# Cineo-6-Channel_Buck_A1.net
KiCad netlist of a schematic drawn in EAGLE
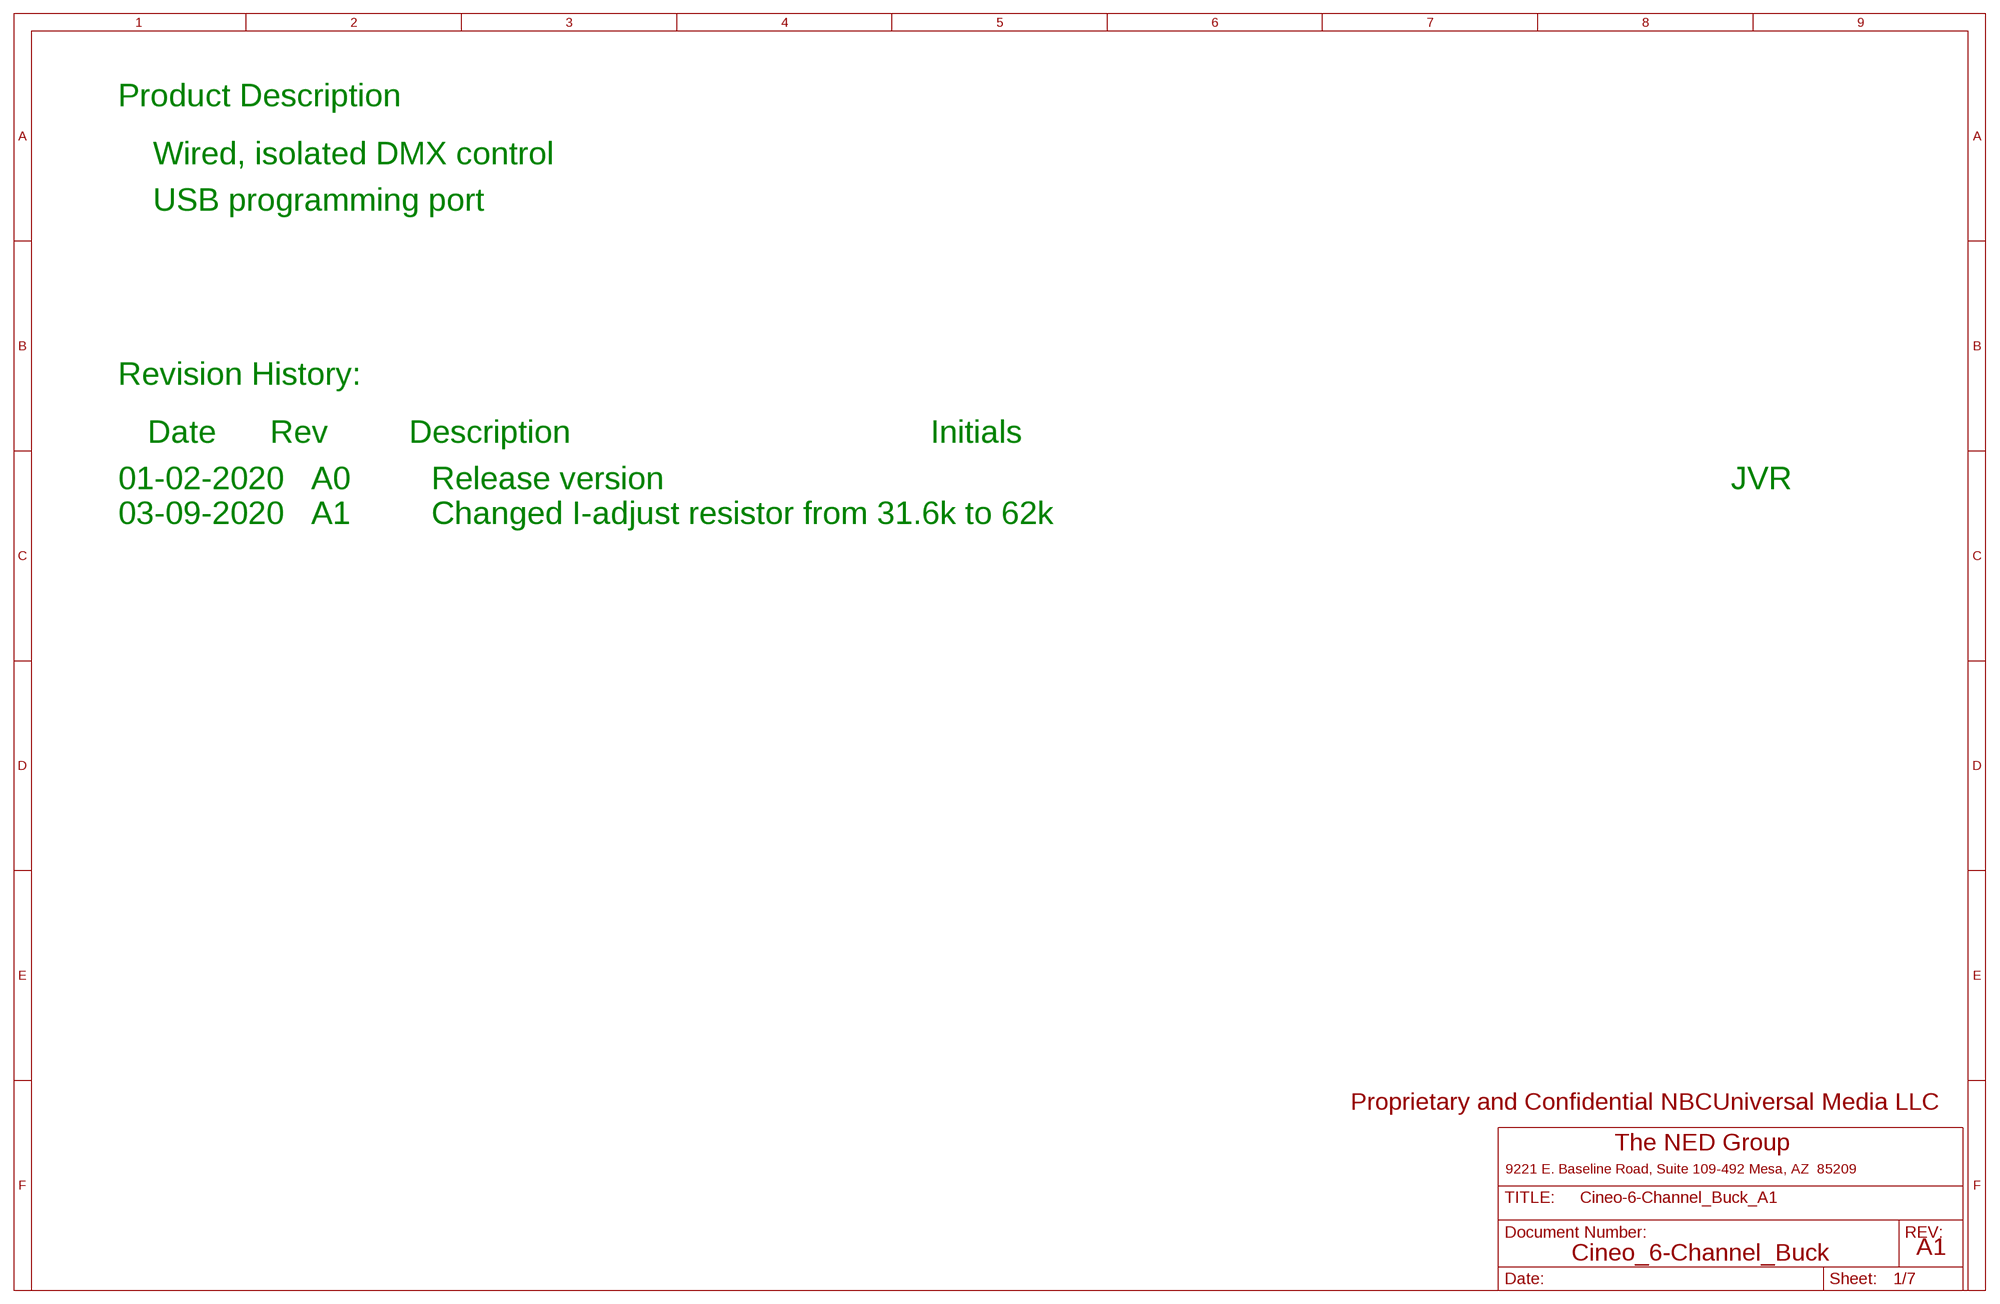
[diagram p0: schematic, sheet 1]
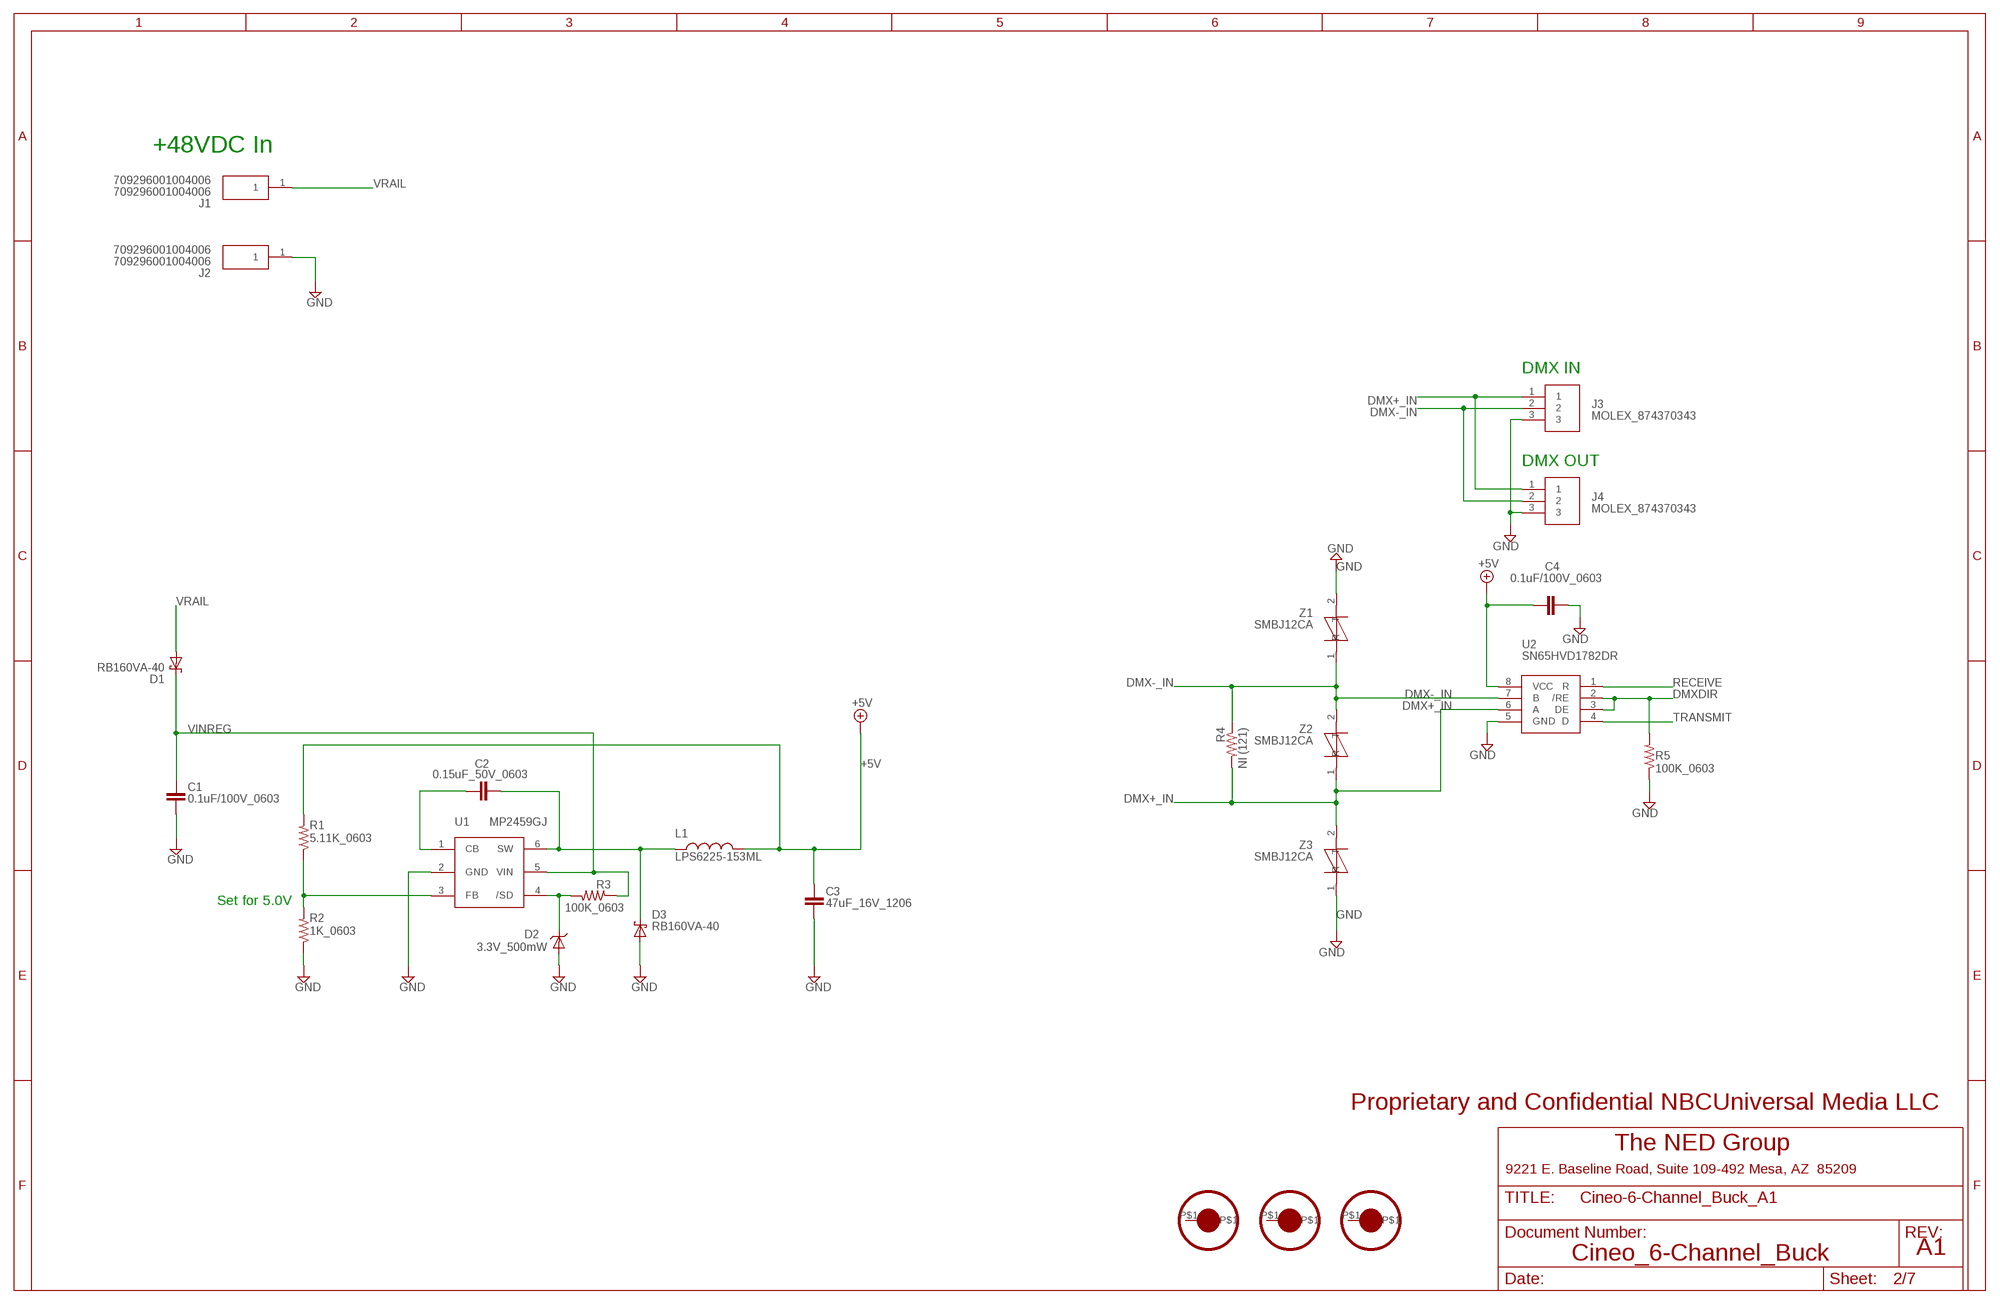
[diagram p1: schematic, sheet 2]
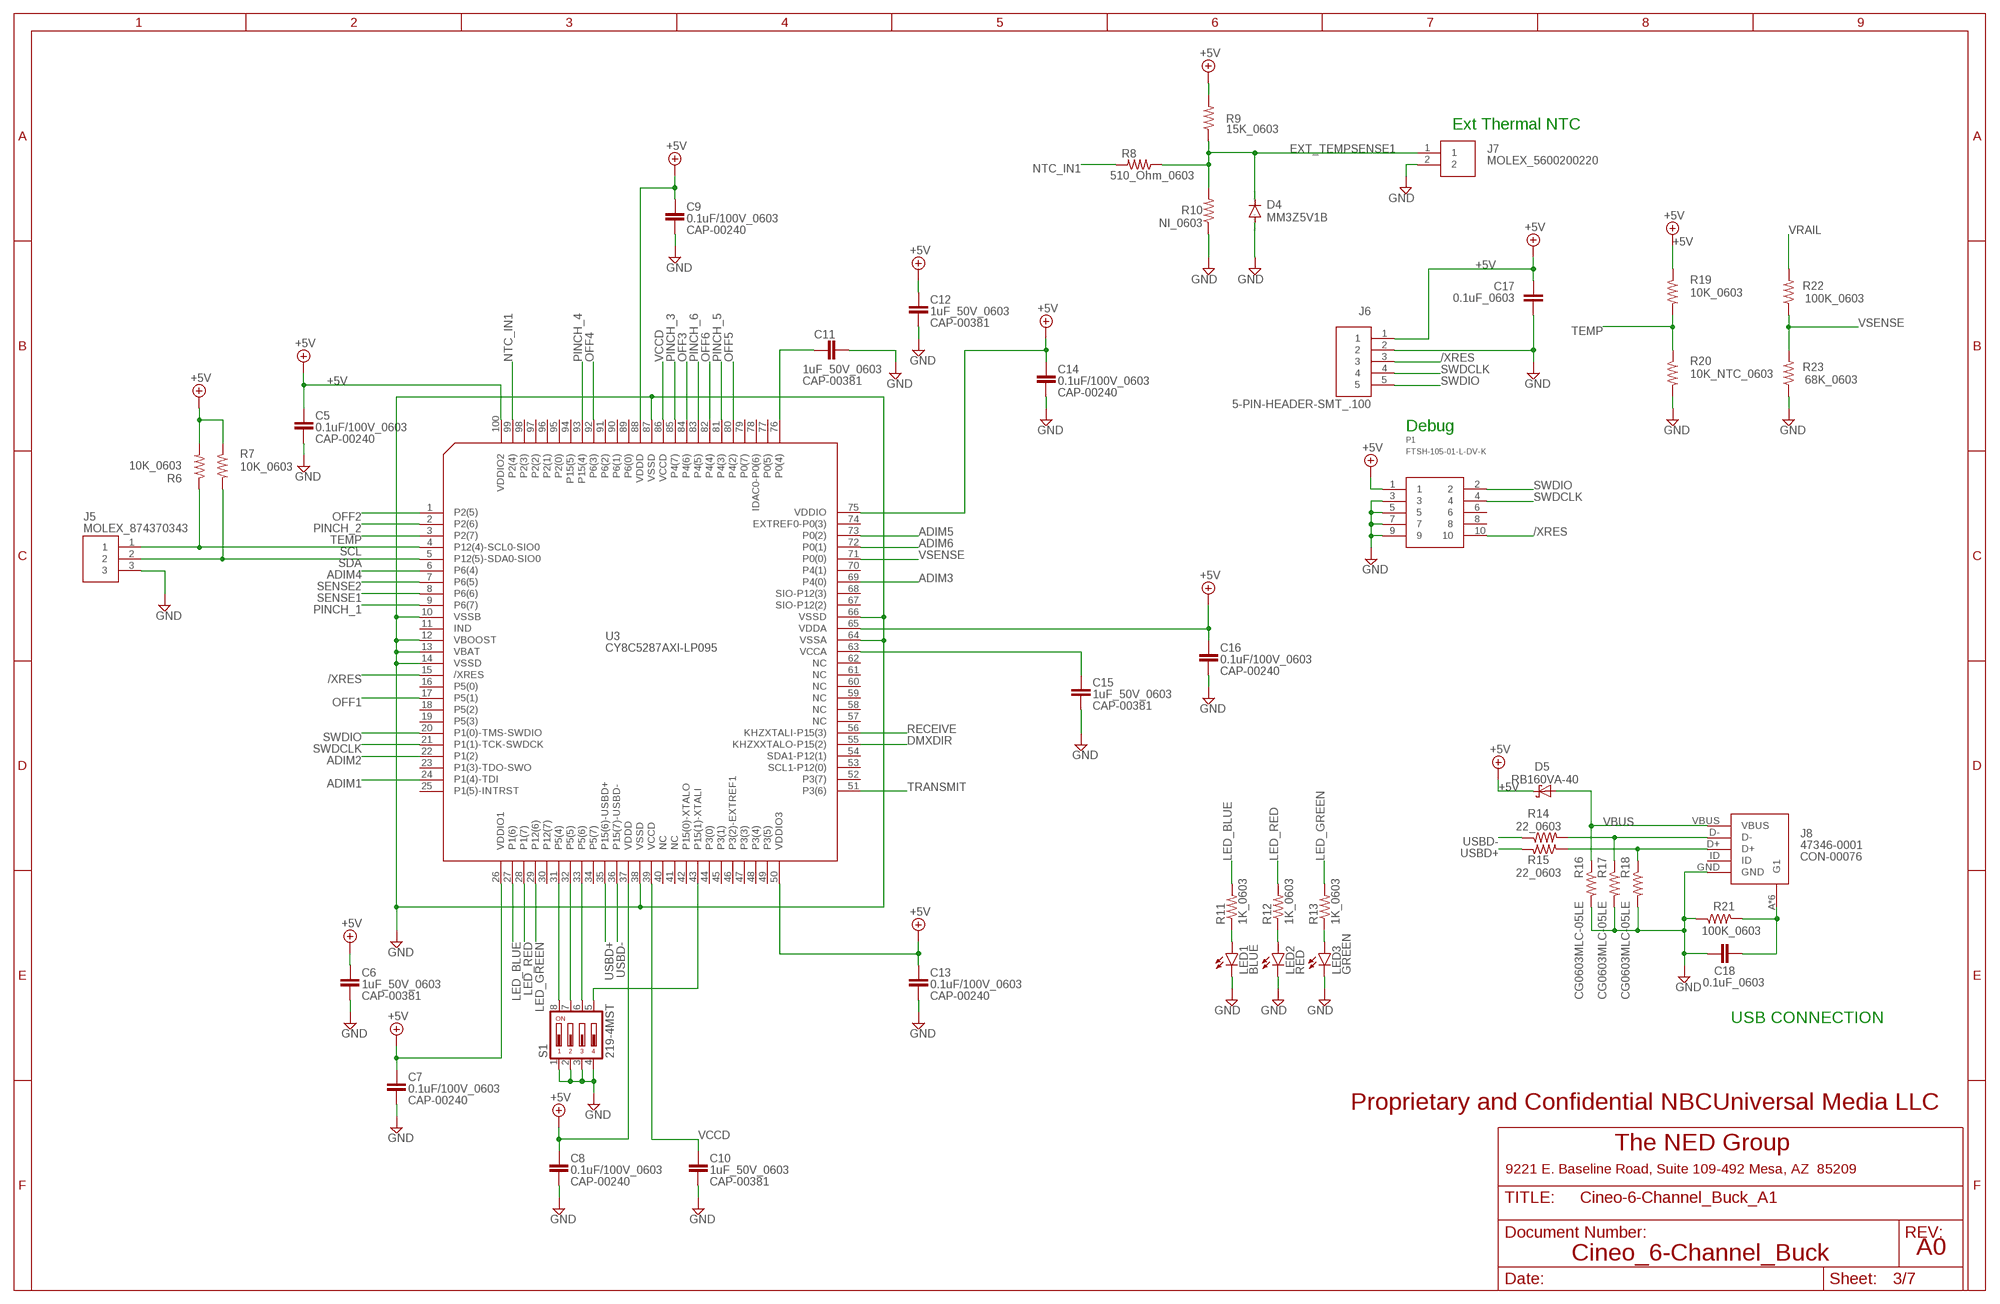
[diagram p2: schematic, sheet 3]
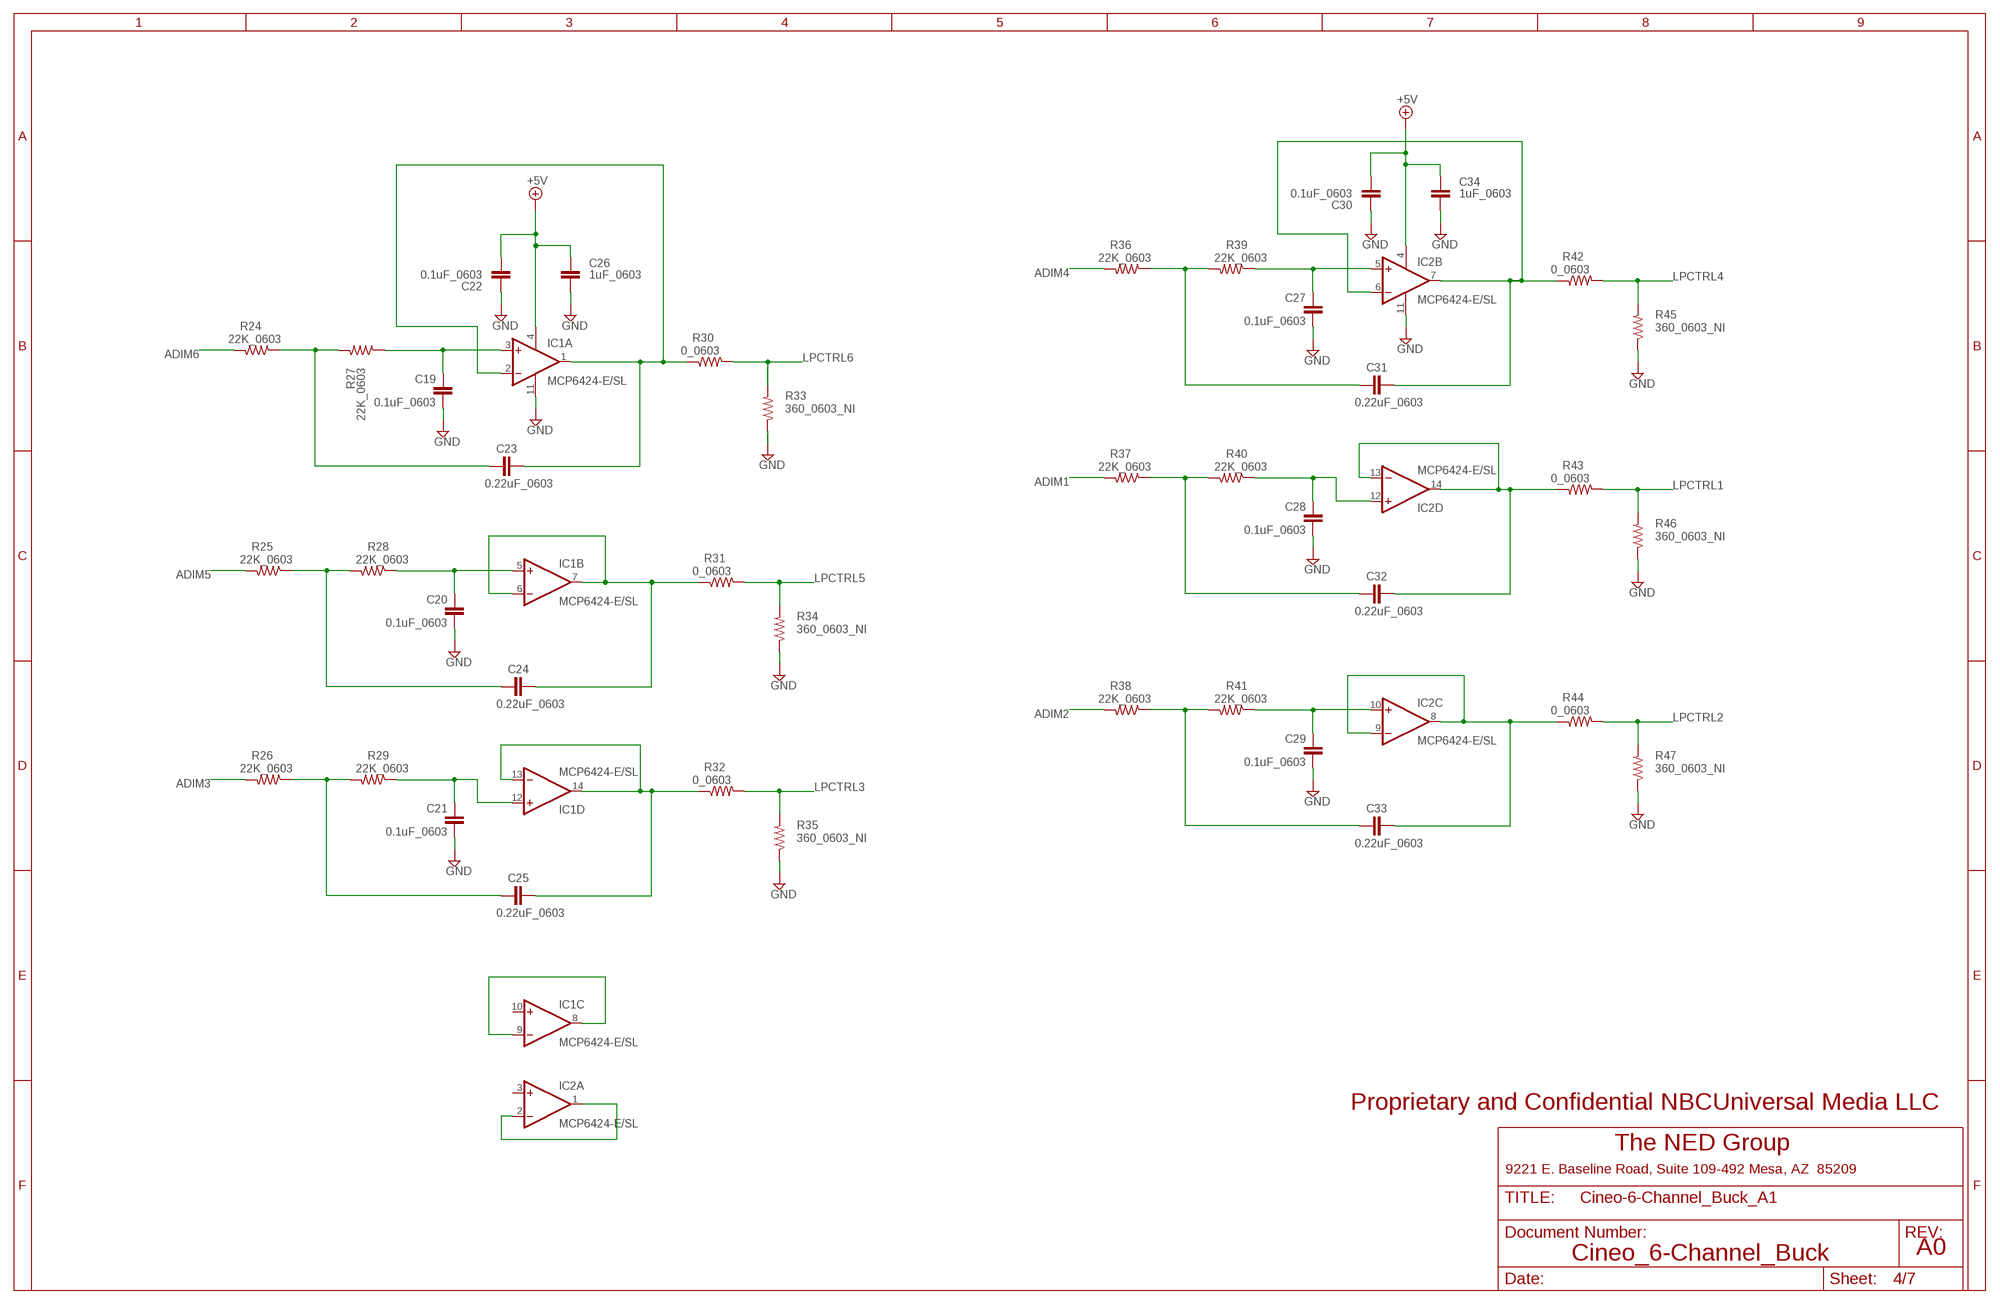
[diagram p3: schematic, sheet 4]
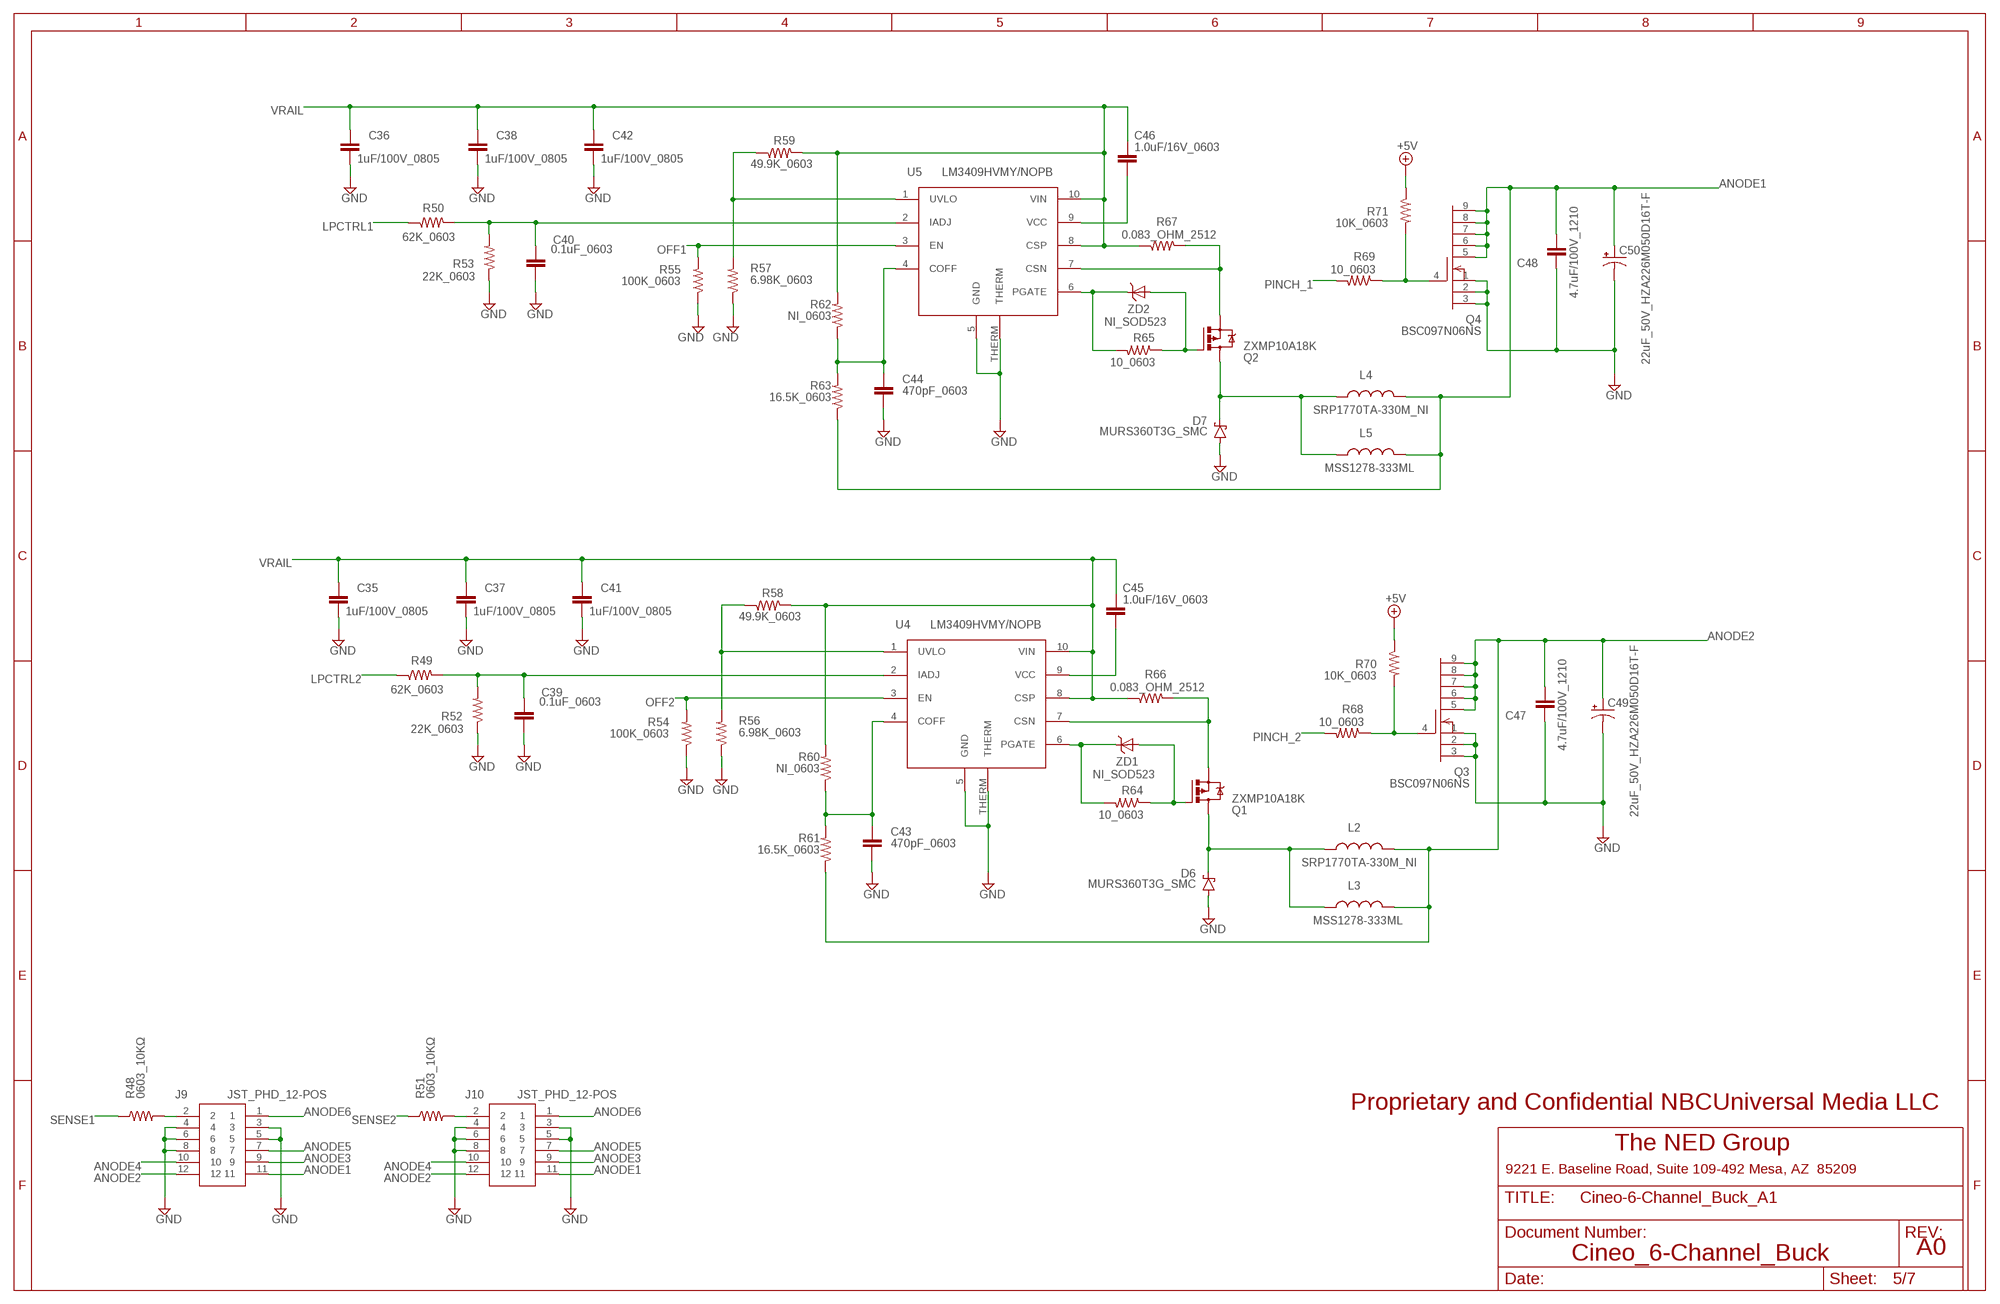
[diagram p4: schematic, sheet 5]
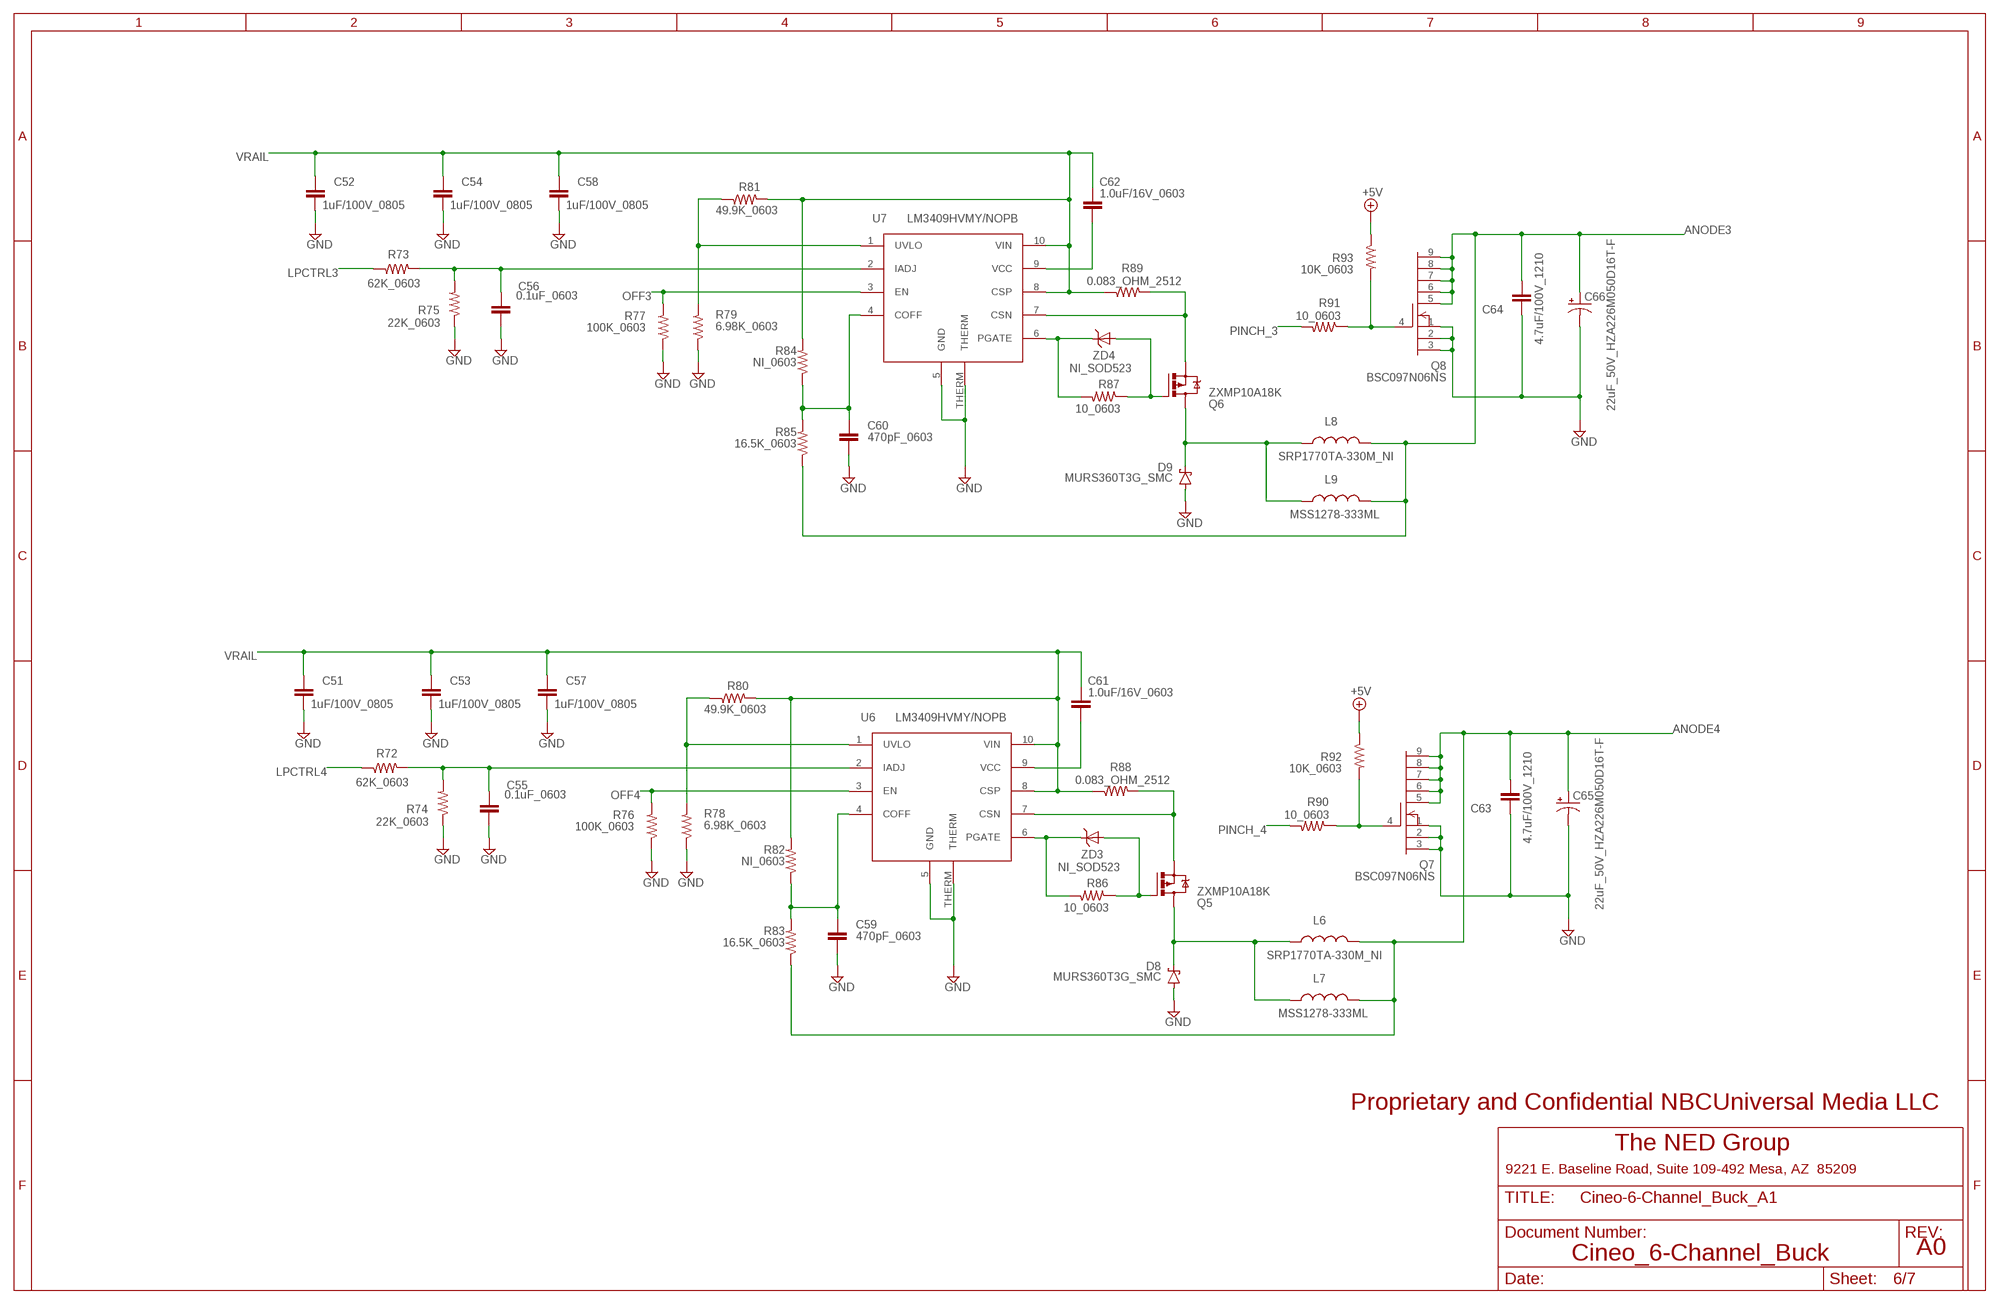
[diagram p5: schematic, sheet 6]
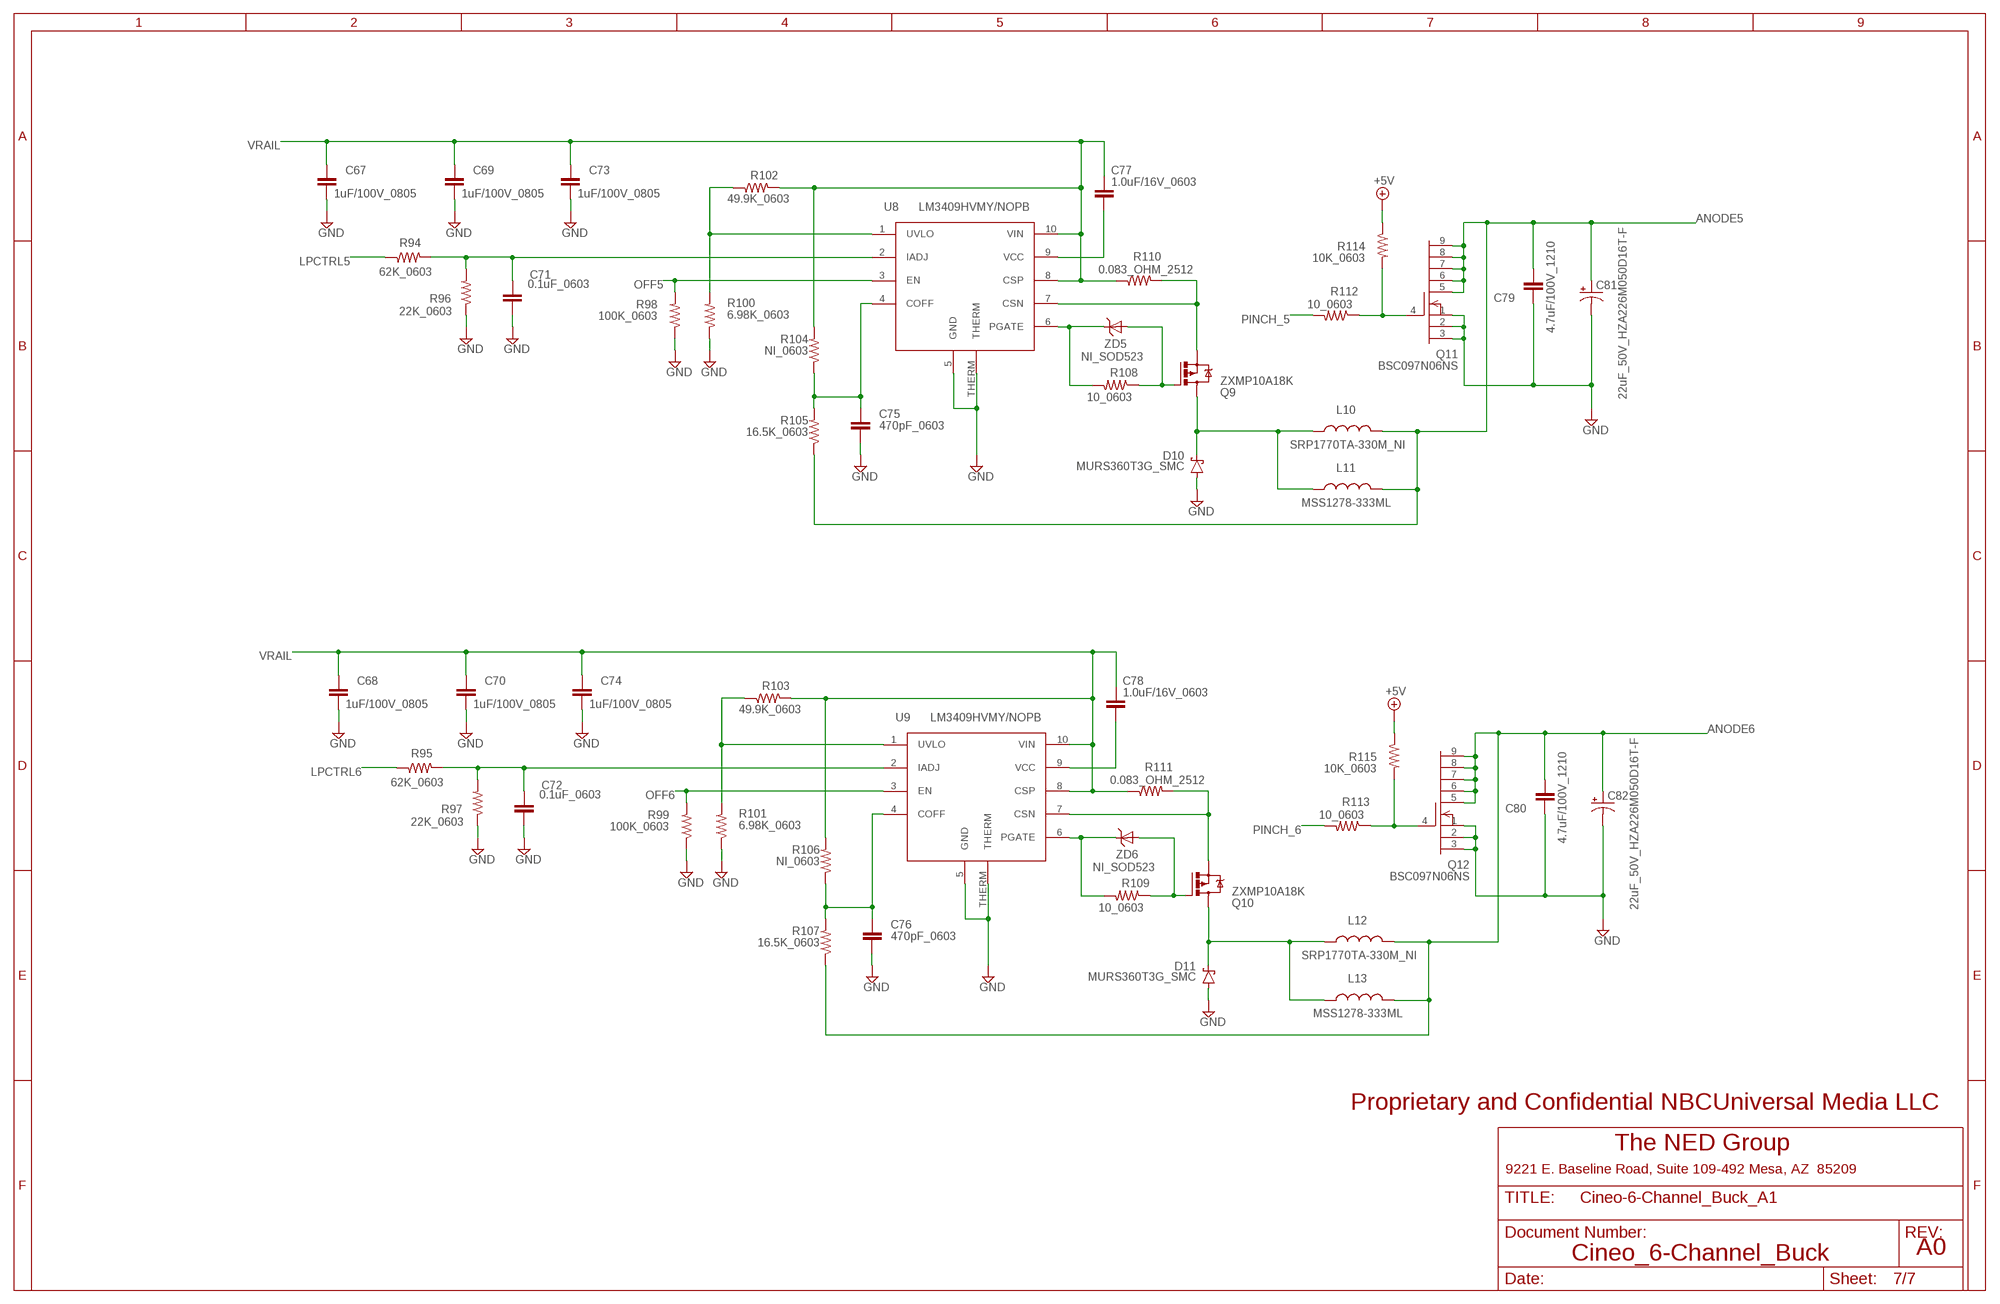
[diagram p6: schematic, sheet 7]

(export (version "E")
  (design (tool "Eeschema 10.0.6"))
  (components
    (comp (ref "C19")
      (value "0.1uF_0603")
      (footprint "eagle-import:C0603")
      (libsource (lib "eagle-import") (part "C-EUC0603"))
    )
    (comp (ref "C20")
      (value "0.1uF_0603")
      (footprint "eagle-import:C0603")
      (libsource (lib "eagle-import") (part "C-EUC0603"))
    )
    (comp (ref "C21")
      (value "0.1uF_0603")
      (footprint "eagle-import:C0603")
      (libsource (lib "eagle-import") (part "C-EUC0603"))
    )
    (comp (ref "C22")
      (value "0.1uF_0603")
      (footprint "eagle-import:C0603")
      (libsource (lib "eagle-import") (part "C-EUC0603"))
    )
    (comp (ref "C23")
      (value "0.22uF_0603")
      (footprint "eagle-import:C0603")
      (libsource (lib "eagle-import") (part "C-EUC0603"))
    )
    (comp (ref "C24")
      (value "0.22uF_0603")
      (footprint "eagle-import:C0603")
      (libsource (lib "eagle-import") (part "C-EUC0603"))
    )
    (comp (ref "C25")
      (value "0.22uF_0603")
      (footprint "eagle-import:C0603")
      (libsource (lib "eagle-import") (part "C-EUC0603"))
    )
    (comp (ref "C26")
      (value "1uF_0603")
      (footprint "eagle-import:C0603")
      (libsource (lib "eagle-import") (part "C-EUC0603"))
    )
    (comp (ref "C27")
      (value "0.1uF_0603")
      (footprint "eagle-import:C0603")
      (libsource (lib "eagle-import") (part "C-EUC0603"))
    )
    (comp (ref "C28")
      (value "0.1uF_0603")
      (footprint "eagle-import:C0603")
      (libsource (lib "eagle-import") (part "C-EUC0603"))
    )
    (comp (ref "C29")
      (value "0.1uF_0603")
      (footprint "eagle-import:C0603")
      (libsource (lib "eagle-import") (part "C-EUC0603"))
    )
    (comp (ref "C30")
      (value "0.1uF_0603")
      (footprint "eagle-import:C0603")
      (libsource (lib "eagle-import") (part "C-EUC0603"))
    )
    (comp (ref "C31")
      (value "0.22uF_0603")
      (footprint "eagle-import:C0603")
      (libsource (lib "eagle-import") (part "C-EUC0603"))
    )
    (comp (ref "C32")
      (value "0.22uF_0603")
      (footprint "eagle-import:C0603")
      (libsource (lib "eagle-import") (part "C-EUC0603"))
    )
    (comp (ref "C33")
      (value "0.22uF_0603")
      (footprint "eagle-import:C0603")
      (libsource (lib "eagle-import") (part "C-EUC0603"))
    )
    (comp (ref "C34")
      (value "1uF_0603")
      (footprint "eagle-import:C0603")
      (libsource (lib "eagle-import") (part "C-EUC0603"))
    )
    (comp (ref "IC1")
      (value "MCP6424-E/SL")
      (footprint "eagle-import:SO14")
      (libsource (lib "eagle-import") (part "TLC274D"))
    )
    (comp (ref "IC2")
      (value "MCP6424-E/SL")
      (footprint "eagle-import:SO14")
      (libsource (lib "eagle-import") (part "TLC274D"))
    )
    (comp (ref "R24")
      (value "22K_0603")
      (footprint "eagle-import:R0603")
      (libsource (lib "eagle-import") (part "R-US_R0603"))
    )
    (comp (ref "R25")
      (value "22K_0603")
      (footprint "eagle-import:R0603")
      (libsource (lib "eagle-import") (part "R-US_R0603"))
    )
    (comp (ref "R26")
      (value "22K_0603")
      (footprint "eagle-import:R0603")
      (libsource (lib "eagle-import") (part "R-US_R0603"))
    )
    (comp (ref "R27")
      (value "22K_0603")
      (footprint "eagle-import:R0603")
      (libsource (lib "eagle-import") (part "R-US_R0603"))
    )
    (comp (ref "R28")
      (value "22K_0603")
      (footprint "eagle-import:R0603")
      (libsource (lib "eagle-import") (part "R-US_R0603"))
    )
    (comp (ref "R29")
      (value "22K_0603")
      (footprint "eagle-import:R0603")
      (libsource (lib "eagle-import") (part "R-US_R0603"))
    )
    (comp (ref "R30")
      (value "0_0603")
      (footprint "eagle-import:R0603")
      (libsource (lib "eagle-import") (part "R-US_R0603"))
    )
    (comp (ref "R31")
      (value "0_0603")
      (footprint "eagle-import:R0603")
      (libsource (lib "eagle-import") (part "R-US_R0603"))
    )
    (comp (ref "R32")
      (value "0_0603")
      (footprint "eagle-import:R0603")
      (libsource (lib "eagle-import") (part "R-US_R0603"))
    )
    (comp (ref "R33")
      (value "360_0603_NI")
      (footprint "eagle-import:R0603")
      (libsource (lib "eagle-import") (part "R-US_R0603"))
    )
    (comp (ref "R34")
      (value "360_0603_NI")
      (footprint "eagle-import:R0603")
      (libsource (lib "eagle-import") (part "R-US_R0603"))
    )
    (comp (ref "R35")
      (value "360_0603_NI")
      (footprint "eagle-import:R0603")
      (libsource (lib "eagle-import") (part "R-US_R0603"))
    )
    (comp (ref "R36")
      (value "22K_0603")
      (footprint "eagle-import:R0603")
      (libsource (lib "eagle-import") (part "R-US_R0603"))
    )
    (comp (ref "R37")
      (value "22K_0603")
      (footprint "eagle-import:R0603")
      (libsource (lib "eagle-import") (part "R-US_R0603"))
    )
    (comp (ref "R38")
      (value "22K_0603")
      (footprint "eagle-import:R0603")
      (libsource (lib "eagle-import") (part "R-US_R0603"))
    )
    (comp (ref "R39")
      (value "22K_0603")
      (footprint "eagle-import:R0603")
      (libsource (lib "eagle-import") (part "R-US_R0603"))
    )
    (comp (ref "R40")
      (value "22K_0603")
      (footprint "eagle-import:R0603")
      (libsource (lib "eagle-import") (part "R-US_R0603"))
    )
    (comp (ref "R41")
      (value "22K_0603")
      (footprint "eagle-import:R0603")
      (libsource (lib "eagle-import") (part "R-US_R0603"))
    )
    (comp (ref "R42")
      (value "0_0603")
      (footprint "eagle-import:R0603")
      (libsource (lib "eagle-import") (part "R-US_R0603"))
    )
    (comp (ref "R43")
      (value "0_0603")
      (footprint "eagle-import:R0603")
      (libsource (lib "eagle-import") (part "R-US_R0603"))
    )
    (comp (ref "R44")
      (value "0_0603")
      (footprint "eagle-import:R0603")
      (libsource (lib "eagle-import") (part "R-US_R0603"))
    )
    (comp (ref "R45")
      (value "360_0603_NI")
      (footprint "eagle-import:R0603")
      (libsource (lib "eagle-import") (part "R-US_R0603"))
    )
    (comp (ref "R46")
      (value "360_0603_NI")
      (footprint "eagle-import:R0603")
      (libsource (lib "eagle-import") (part "R-US_R0603"))
    )
    (comp (ref "R47")
      (value "360_0603_NI")
      (footprint "eagle-import:R0603")
      (libsource (lib "eagle-import") (part "R-US_R0603"))
    )
    (comp (ref "C67")
      (value "1uF/100V_0805")
      (footprint "eagle-import:C0805")
      (libsource (lib "eagle-import") (part "C-EUC0805"))
    )
    (comp (ref "C68")
      (value "1uF/100V_0805")
      (footprint "eagle-import:C0805")
      (libsource (lib "eagle-import") (part "C-EUC0805"))
    )
    (comp (ref "C69")
      (value "1uF/100V_0805")
      (footprint "eagle-import:C0805")
      (libsource (lib "eagle-import") (part "C-EUC0805"))
    )
    (comp (ref "C70")
      (value "1uF/100V_0805")
      (footprint "eagle-import:C0805")
      (libsource (lib "eagle-import") (part "C-EUC0805"))
    )
    (comp (ref "C71")
      (value "0.1uF_0603")
      (footprint "eagle-import:C0603")
      (libsource (lib "eagle-import") (part "C-EUC0603"))
    )
    (comp (ref "C72")
      (value "0.1uF_0603")
      (footprint "eagle-import:C0603")
      (libsource (lib "eagle-import") (part "C-EUC0603"))
    )
    (comp (ref "C73")
      (value "1uF/100V_0805")
      (footprint "eagle-import:C0805")
      (libsource (lib "eagle-import") (part "C-EUC0805"))
    )
    (comp (ref "C74")
      (value "1uF/100V_0805")
      (footprint "eagle-import:C0805")
      (libsource (lib "eagle-import") (part "C-EUC0805"))
    )
    (comp (ref "C75")
      (value "470pF_0603")
      (footprint "eagle-import:C0603")
      (libsource (lib "eagle-import") (part "C-EUC0603"))
    )
    (comp (ref "C76")
      (value "470pF_0603")
      (footprint "eagle-import:C0603")
      (libsource (lib "eagle-import") (part "C-EUC0603"))
    )
    (comp (ref "C77")
      (value "1.0uF/16V_0603")
      (footprint "eagle-import:C0603")
      (libsource (lib "eagle-import") (part "C-EUC0603"))
    )
    (comp (ref "C78")
      (value "1.0uF/16V_0603")
      (footprint "eagle-import:C0603")
      (libsource (lib "eagle-import") (part "C-EUC0603"))
    )
    (comp (ref "C79")
      (value "4.7uF/100V_1210")
      (footprint "eagle-import:C1210")
      (libsource (lib "eagle-import") (part "C-EUC1210"))
    )
    (comp (ref "C80")
      (value "4.7uF/100V_1210")
      (footprint "eagle-import:C1210")
      (libsource (lib "eagle-import") (part "C-EUC1210"))
    )
    (comp (ref "C81")
      (value "22uF_50V_HZA226M050D16T-F")
      (footprint "eagle-import:PANASONIC_D")
      (libsource (lib "eagle-import") (part "CPOL-USD"))
    )
    (comp (ref "C82")
      (value "22uF_50V_HZA226M050D16T-F")
      (footprint "eagle-import:PANASONIC_D")
      (libsource (lib "eagle-import") (part "CPOL-USD"))
    )
    (comp (ref "D10")
      (value "MURS360T3G_SMC")
      (footprint "eagle-import:SMC")
      (libsource (lib "eagle-import") (part "SCHOTTKY-DIODESMC"))
    )
    (comp (ref "D11")
      (value "MURS360T3G_SMC")
      (footprint "eagle-import:SMC")
      (libsource (lib "eagle-import") (part "SCHOTTKY-DIODESMC"))
    )
    (comp (ref "L10")
      (value "SRP1770TA-330M_NI")
      (footprint "eagle-import:BOURNS_SRP1770TA")
      (libsource (lib "eagle-import") (part "BOURNS_SRP1770TA"))
    )
    (comp (ref "L11")
      (value "MSS1278-333ML")
      (footprint "eagle-import:MSS1260")
      (libsource (lib "eagle-import") (part "COILCRAFT_MSS1260"))
    )
    (comp (ref "L12")
      (value "SRP1770TA-330M_NI")
      (footprint "eagle-import:BOURNS_SRP1770TA")
      (libsource (lib "eagle-import") (part "BOURNS_SRP1770TA"))
    )
    (comp (ref "L13")
      (value "MSS1278-333ML")
      (footprint "eagle-import:MSS1260")
      (libsource (lib "eagle-import") (part "COILCRAFT_MSS1260"))
    )
    (comp (ref "Q9")
      (value "ZXMP10A18K")
      (footprint "eagle-import:DPAK")
      (libsource (lib "eagle-import") (part "MOSFET_P-CHANNEL_3LEADTAB_SOURCE"))
    )
    (comp (ref "Q10")
      (value "ZXMP10A18K")
      (footprint "eagle-import:DPAK")
      (libsource (lib "eagle-import") (part "MOSFET_P-CHANNEL_3LEADTAB_SOURCE"))
    )
    (comp (ref "Q11")
      (value "BSC097N06NS")
      (footprint "eagle-import:SO-8_POWERPAC")
      (libsource (lib "eagle-import") (part "SI7464DP_SO8_POWERPAC"))
    )
    (comp (ref "Q12")
      (value "BSC097N06NS")
      (footprint "eagle-import:SO-8_POWERPAC")
      (libsource (lib "eagle-import") (part "SI7464DP_SO8_POWERPAC"))
    )
    (comp (ref "R94")
      (value "62K_0603")
      (footprint "eagle-import:R0603")
      (libsource (lib "eagle-import") (part "R-US_R0603"))
    )
    (comp (ref "R95")
      (value "62K_0603")
      (footprint "eagle-import:R0603")
      (libsource (lib "eagle-import") (part "R-US_R0603"))
    )
    (comp (ref "R96")
      (value "22K_0603")
      (footprint "eagle-import:R0603")
      (libsource (lib "eagle-import") (part "R-US_R0603"))
    )
    (comp (ref "R97")
      (value "22K_0603")
      (footprint "eagle-import:R0603")
      (libsource (lib "eagle-import") (part "R-US_R0603"))
    )
    (comp (ref "R98")
      (value "100K_0603")
      (footprint "eagle-import:R0603")
      (libsource (lib "eagle-import") (part "R-US_R0603"))
    )
    (comp (ref "R99")
      (value "100K_0603")
      (footprint "eagle-import:R0603")
      (libsource (lib "eagle-import") (part "R-US_R0603"))
    )
    (comp (ref "R100")
      (value "6.98K_0603")
      (footprint "eagle-import:R0603")
      (libsource (lib "eagle-import") (part "R-US_R0603"))
    )
    (comp (ref "R101")
      (value "6.98K_0603")
      (footprint "eagle-import:R0603")
      (libsource (lib "eagle-import") (part "R-US_R0603"))
    )
    (comp (ref "R102")
      (value "49.9K_0603")
      (footprint "eagle-import:R0603")
      (libsource (lib "eagle-import") (part "R-US_R0603"))
    )
    (comp (ref "R103")
      (value "49.9K_0603")
      (footprint "eagle-import:R0603")
      (libsource (lib "eagle-import") (part "R-US_R0603"))
    )
    (comp (ref "R104")
      (value "NI_0603")
      (footprint "eagle-import:R0603")
      (libsource (lib "eagle-import") (part "R-US_R0603"))
    )
    (comp (ref "R105")
      (value "16.5K_0603")
      (footprint "eagle-import:R0603")
      (libsource (lib "eagle-import") (part "R-US_R0603"))
    )
    (comp (ref "R106")
      (value "NI_0603")
      (footprint "eagle-import:R0603")
      (libsource (lib "eagle-import") (part "R-US_R0603"))
    )
    (comp (ref "R107")
      (value "16.5K_0603")
      (footprint "eagle-import:R0603")
      (libsource (lib "eagle-import") (part "R-US_R0603"))
    )
    (comp (ref "R108")
      (value "10_0603")
      (footprint "eagle-import:R0603")
      (libsource (lib "eagle-import") (part "R-US_R0603"))
    )
    (comp (ref "R109")
      (value "10_0603")
      (footprint "eagle-import:R0603")
      (libsource (lib "eagle-import") (part "R-US_R0603"))
    )
    (comp (ref "R110")
      (value "0.083_OHM_2512")
      (footprint "eagle-import:R2512")
      (libsource (lib "eagle-import") (part "R-US_R2512"))
    )
    (comp (ref "R111")
      (value "0.083_OHM_2512")
      (footprint "eagle-import:R2512")
      (libsource (lib "eagle-import") (part "R-US_R2512"))
    )
    (comp (ref "R112")
      (value "10_0603")
      (footprint "eagle-import:R0603")
      (libsource (lib "eagle-import") (part "R-US_R0603"))
    )
    (comp (ref "R113")
      (value "10_0603")
      (footprint "eagle-import:R0603")
      (libsource (lib "eagle-import") (part "R-US_R0603"))
    )
    (comp (ref "R114")
      (value "10K_0603")
      (footprint "eagle-import:R0603")
      (libsource (lib "eagle-import") (part "R-US_R0603"))
    )
    (comp (ref "R115")
      (value "10K_0603")
      (footprint "eagle-import:R0603")
      (libsource (lib "eagle-import") (part "R-US_R0603"))
    )
    (comp (ref "U8")
      (value "LM3409HVMY/NOPB")
      (footprint "eagle-import:MSOP10-THERMALENHANCED")
      (libsource (lib "eagle-import") (part "LM3409HV"))
    )
    (comp (ref "U9")
      (value "LM3409HVMY/NOPB")
      (footprint "eagle-import:MSOP10-THERMALENHANCED")
      (libsource (lib "eagle-import") (part "LM3409HV"))
    )
    (comp (ref "ZD5")
      (value "NI_SOD523")
      (footprint "eagle-import:SOD-523")
      (libsource (lib "eagle-import") (part "ZENER_SOD-523"))
    )
    (comp (ref "ZD6")
      (value "NI_SOD523")
      (footprint "eagle-import:SOD-523")
      (libsource (lib "eagle-import") (part "ZENER_SOD-523"))
    )
    (comp (ref "C35")
      (value "1uF/100V_0805")
      (footprint "eagle-import:C0805")
      (libsource (lib "eagle-import") (part "C-EUC0805"))
    )
    (comp (ref "C36")
      (value "1uF/100V_0805")
      (footprint "eagle-import:C0805")
      (libsource (lib "eagle-import") (part "C-EUC0805"))
    )
    (comp (ref "C37")
      (value "1uF/100V_0805")
      (footprint "eagle-import:C0805")
      (libsource (lib "eagle-import") (part "C-EUC0805"))
    )
    (comp (ref "C38")
      (value "1uF/100V_0805")
      (footprint "eagle-import:C0805")
      (libsource (lib "eagle-import") (part "C-EUC0805"))
    )
    (comp (ref "C39")
      (value "0.1uF_0603")
      (footprint "eagle-import:C0603")
      (libsource (lib "eagle-import") (part "C-EUC0603"))
    )
    (comp (ref "C40")
      (value "0.1uF_0603")
      (footprint "eagle-import:C0603")
      (libsource (lib "eagle-import") (part "C-EUC0603"))
    )
    (comp (ref "C41")
      (value "1uF/100V_0805")
      (footprint "eagle-import:C0805")
      (libsource (lib "eagle-import") (part "C-EUC0805"))
    )
    (comp (ref "C42")
      (value "1uF/100V_0805")
      (footprint "eagle-import:C0805")
      (libsource (lib "eagle-import") (part "C-EUC0805"))
    )
    (comp (ref "C43")
      (value "470pF_0603")
      (footprint "eagle-import:C0603")
      (libsource (lib "eagle-import") (part "C-EUC0603"))
    )
    (comp (ref "C44")
      (value "470pF_0603")
      (footprint "eagle-import:C0603")
      (libsource (lib "eagle-import") (part "C-EUC0603"))
    )
    (comp (ref "C45")
      (value "1.0uF/16V_0603")
      (footprint "eagle-import:C0603")
      (libsource (lib "eagle-import") (part "C-EUC0603"))
    )
    (comp (ref "C46")
      (value "1.0uF/16V_0603")
      (footprint "eagle-import:C0603")
      (libsource (lib "eagle-import") (part "C-EUC0603"))
    )
    (comp (ref "C47")
      (value "4.7uF/100V_1210")
      (footprint "eagle-import:C1210")
      (libsource (lib "eagle-import") (part "C-EUC1210"))
    )
    (comp (ref "C48")
      (value "4.7uF/100V_1210")
      (footprint "eagle-import:C1210")
      (libsource (lib "eagle-import") (part "C-EUC1210"))
    )
    (comp (ref "C49")
      (value "22uF_50V_HZA226M050D16T-F")
      (footprint "eagle-import:PANASONIC_D")
      (libsource (lib "eagle-import") (part "CPOL-USD"))
    )
    (comp (ref "C50")
      (value "22uF_50V_HZA226M050D16T-F")
      (footprint "eagle-import:PANASONIC_D")
      (libsource (lib "eagle-import") (part "CPOL-USD"))
    )
    (comp (ref "D6")
      (value "MURS360T3G_SMC")
      (footprint "eagle-import:SMC")
      (libsource (lib "eagle-import") (part "SCHOTTKY-DIODESMC"))
    )
    (comp (ref "D7")
      (value "MURS360T3G_SMC")
      (footprint "eagle-import:SMC")
      (libsource (lib "eagle-import") (part "SCHOTTKY-DIODESMC"))
    )
    (comp (ref "J9")
      (value "JST_PHD_12-POS")
      (footprint "eagle-import:JST_PHD_12-POS")
      (libsource (lib "eagle-import") (part "JST_PHD_12-POS"))
    )
    (comp (ref "J10")
      (value "JST_PHD_12-POS")
      (footprint "eagle-import:JST_PHD_12-POS")
      (libsource (lib "eagle-import") (part "JST_PHD_12-POS"))
    )
    (comp (ref "L2")
      (value "SRP1770TA-330M_NI")
      (footprint "eagle-import:BOURNS_SRP1770TA")
      (libsource (lib "eagle-import") (part "BOURNS_SRP1770TA"))
    )
    (comp (ref "L3")
      (value "MSS1278-333ML")
      (footprint "eagle-import:MSS1260")
      (libsource (lib "eagle-import") (part "COILCRAFT_MSS1260"))
    )
    (comp (ref "L4")
      (value "SRP1770TA-330M_NI")
      (footprint "eagle-import:BOURNS_SRP1770TA")
      (libsource (lib "eagle-import") (part "BOURNS_SRP1770TA"))
    )
    (comp (ref "L5")
      (value "MSS1278-333ML")
      (footprint "eagle-import:MSS1260")
      (libsource (lib "eagle-import") (part "COILCRAFT_MSS1260"))
    )
    (comp (ref "Q1")
      (value "ZXMP10A18K")
      (footprint "eagle-import:DPAK")
      (libsource (lib "eagle-import") (part "MOSFET_P-CHANNEL_3LEADTAB_SOURCE"))
    )
    (comp (ref "Q2")
      (value "ZXMP10A18K")
      (footprint "eagle-import:DPAK")
      (libsource (lib "eagle-import") (part "MOSFET_P-CHANNEL_3LEADTAB_SOURCE"))
    )
    (comp (ref "Q3")
      (value "BSC097N06NS")
      (footprint "eagle-import:SO-8_POWERPAC")
      (libsource (lib "eagle-import") (part "SI7464DP_SO8_POWERPAC"))
    )
    (comp (ref "Q4")
      (value "BSC097N06NS")
      (footprint "eagle-import:SO-8_POWERPAC")
      (libsource (lib "eagle-import") (part "SI7464DP_SO8_POWERPAC"))
    )
    (comp (ref "R48")
      (value "0603_10KΩ")
      (footprint "eagle-import:R0603")
      (fields (field (name "PART_NUM") "RES-00001"))
      (libsource (lib "eagle-import") (part "0603_10KΩ"))
    )
    (comp (ref "R49")
      (value "62K_0603")
      (footprint "eagle-import:R0603")
      (libsource (lib "eagle-import") (part "R-US_R0603"))
    )
    (comp (ref "R50")
      (value "62K_0603")
      (footprint "eagle-import:R0603")
      (libsource (lib "eagle-import") (part "R-US_R0603"))
    )
    (comp (ref "R51")
      (value "0603_10KΩ")
      (footprint "eagle-import:R0603")
      (fields (field (name "PART_NUM") "RES-00001"))
      (libsource (lib "eagle-import") (part "0603_10KΩ"))
    )
    (comp (ref "R52")
      (value "22K_0603")
      (footprint "eagle-import:R0603")
      (libsource (lib "eagle-import") (part "R-US_R0603"))
    )
    (comp (ref "R53")
      (value "22K_0603")
      (footprint "eagle-import:R0603")
      (libsource (lib "eagle-import") (part "R-US_R0603"))
    )
    (comp (ref "R54")
      (value "100K_0603")
      (footprint "eagle-import:R0603")
      (libsource (lib "eagle-import") (part "R-US_R0603"))
    )
    (comp (ref "R55")
      (value "100K_0603")
      (footprint "eagle-import:R0603")
      (libsource (lib "eagle-import") (part "R-US_R0603"))
    )
    (comp (ref "R56")
      (value "6.98K_0603")
      (footprint "eagle-import:R0603")
      (libsource (lib "eagle-import") (part "R-US_R0603"))
    )
    (comp (ref "R57")
      (value "6.98K_0603")
      (footprint "eagle-import:R0603")
      (libsource (lib "eagle-import") (part "R-US_R0603"))
    )
    (comp (ref "R58")
      (value "49.9K_0603")
      (footprint "eagle-import:R0603")
      (libsource (lib "eagle-import") (part "R-US_R0603"))
    )
    (comp (ref "R59")
      (value "49.9K_0603")
      (footprint "eagle-import:R0603")
      (libsource (lib "eagle-import") (part "R-US_R0603"))
    )
    (comp (ref "R60")
      (value "NI_0603")
      (footprint "eagle-import:R0603")
      (libsource (lib "eagle-import") (part "R-US_R0603"))
    )
    (comp (ref "R61")
      (value "16.5K_0603")
      (footprint "eagle-import:R0603")
      (libsource (lib "eagle-import") (part "R-US_R0603"))
    )
    (comp (ref "R62")
      (value "NI_0603")
      (footprint "eagle-import:R0603")
      (libsource (lib "eagle-import") (part "R-US_R0603"))
    )
    (comp (ref "R63")
      (value "16.5K_0603")
      (footprint "eagle-import:R0603")
      (libsource (lib "eagle-import") (part "R-US_R0603"))
    )
    (comp (ref "R64")
      (value "10_0603")
      (footprint "eagle-import:R0603")
      (libsource (lib "eagle-import") (part "R-US_R0603"))
    )
    (comp (ref "R65")
      (value "10_0603")
      (footprint "eagle-import:R0603")
      (libsource (lib "eagle-import") (part "R-US_R0603"))
    )
    (comp (ref "R66")
      (value "0.083_OHM_2512")
      (footprint "eagle-import:R2512")
      (libsource (lib "eagle-import") (part "R-US_R2512"))
    )
    (comp (ref "R67")
      (value "0.083_OHM_2512")
      (footprint "eagle-import:R2512")
      (libsource (lib "eagle-import") (part "R-US_R2512"))
    )
    (comp (ref "R68")
      (value "10_0603")
      (footprint "eagle-import:R0603")
      (libsource (lib "eagle-import") (part "R-US_R0603"))
    )
    (comp (ref "R69")
      (value "10_0603")
      (footprint "eagle-import:R0603")
      (libsource (lib "eagle-import") (part "R-US_R0603"))
    )
    (comp (ref "R70")
      (value "10K_0603")
      (footprint "eagle-import:R0603")
      (libsource (lib "eagle-import") (part "R-US_R0603"))
    )
    (comp (ref "R71")
      (value "10K_0603")
      (footprint "eagle-import:R0603")
      (libsource (lib "eagle-import") (part "R-US_R0603"))
    )
    (comp (ref "U4")
      (value "LM3409HVMY/NOPB")
      (footprint "eagle-import:MSOP10-THERMALENHANCED")
      (libsource (lib "eagle-import") (part "LM3409HV"))
    )
    (comp (ref "U5")
      (value "LM3409HVMY/NOPB")
      (footprint "eagle-import:MSOP10-THERMALENHANCED")
      (libsource (lib "eagle-import") (part "LM3409HV"))
    )
    (comp (ref "ZD1")
      (value "NI_SOD523")
      (footprint "eagle-import:SOD-523")
      (libsource (lib "eagle-import") (part "ZENER_SOD-523"))
    )
    (comp (ref "ZD2")
      (value "NI_SOD523")
      (footprint "eagle-import:SOD-523")
      (libsource (lib "eagle-import") (part "ZENER_SOD-523"))
    )
    (comp (ref "C5")
      (value "0.1uF/100V_0603")
      (footprint "eagle-import:C0603")
      (fields (field (name "PART_NUM") "CAP-00240"))
      (libsource (lib "eagle-import") (part "0603_0.1UF_100V"))
    )
    (comp (ref "C6")
      (value "1uF_50V_0603")
      (footprint "eagle-import:C0603")
      (fields (field (name "PART_NUM") "CAP-00381"))
      (libsource (lib "eagle-import") (part "0603_1UF_50V"))
    )
    (comp (ref "C7")
      (value "0.1uF/100V_0603")
      (footprint "eagle-import:C0603")
      (fields (field (name "PART_NUM") "CAP-00240"))
      (libsource (lib "eagle-import") (part "0603_0.1UF_100V"))
    )
    (comp (ref "C8")
      (value "0.1uF/100V_0603")
      (footprint "eagle-import:C0603")
      (fields (field (name "PART_NUM") "CAP-00240"))
      (libsource (lib "eagle-import") (part "0603_0.1UF_100V"))
    )
    (comp (ref "C9")
      (value "0.1uF/100V_0603")
      (footprint "eagle-import:C0603")
      (fields (field (name "PART_NUM") "CAP-00240"))
      (libsource (lib "eagle-import") (part "0603_0.1UF_100V"))
    )
    (comp (ref "C10")
      (value "1uF_50V_0603")
      (footprint "eagle-import:C0603")
      (fields (field (name "PART_NUM") "CAP-00381"))
      (libsource (lib "eagle-import") (part "0603_1UF_50V"))
    )
    (comp (ref "C11")
      (value "1uF_50V_0603")
      (footprint "eagle-import:C0603")
      (fields (field (name "PART_NUM") "CAP-00381"))
      (libsource (lib "eagle-import") (part "0603_1UF_50V"))
    )
    (comp (ref "C12")
      (value "1uF_50V_0603")
      (footprint "eagle-import:C0603")
      (fields (field (name "PART_NUM") "CAP-00381"))
      (libsource (lib "eagle-import") (part "0603_1UF_50V"))
    )
    (comp (ref "C13")
      (value "0.1uF/100V_0603")
      (footprint "eagle-import:C0603")
      (fields (field (name "PART_NUM") "CAP-00240"))
      (libsource (lib "eagle-import") (part "0603_0.1UF_100V"))
    )
    (comp (ref "C14")
      (value "0.1uF/100V_0603")
      (footprint "eagle-import:C0603")
      (fields (field (name "PART_NUM") "CAP-00240"))
      (libsource (lib "eagle-import") (part "0603_0.1UF_100V"))
    )
    (comp (ref "C15")
      (value "1uF_50V_0603")
      (footprint "eagle-import:C0603")
      (fields (field (name "PART_NUM") "CAP-00381"))
      (libsource (lib "eagle-import") (part "0603_1UF_50V"))
    )
    (comp (ref "C16")
      (value "0.1uF/100V_0603")
      (footprint "eagle-import:C0603")
      (fields (field (name "PART_NUM") "CAP-00240"))
      (libsource (lib "eagle-import") (part "0603_0.1UF_100V"))
    )
    (comp (ref "C17")
      (value "0.1uF_0603")
      (footprint "eagle-import:C0603")
      (libsource (lib "eagle-import") (part "C-EUC0603"))
    )
    (comp (ref "C18")
      (value "0.1uF_0603")
      (footprint "eagle-import:C0603")
      (libsource (lib "eagle-import") (part "C-EUC0603"))
    )
    (comp (ref "D4")
      (value "MM3Z5V1B")
      (footprint "eagle-import:SOD323-R")
      (libsource (lib "eagle-import") (part "DIODE-SOD323-R"))
    )
    (comp (ref "D5")
      (value "RB160VA-40")
      (footprint "eagle-import:TUMD2")
      (libsource (lib "eagle-import") (part "RSX051VA-30"))
    )
    (comp (ref "J5")
      (value "MOLEX_874370343")
      (footprint "eagle-import:MOLEX_874370343")
      (libsource (lib "eagle-import") (part "MOLEX_874370343"))
    )
    (comp (ref "J6")
      (value "5-PIN-HEADER-SMT_.100")
      (footprint "eagle-import:5-PIN_SMT_.100")
      (fields (field (name "PART_NUM") "NOT INSTALLED"))
      (libsource (lib "eagle-import") (part "5-PIN-HEADER-SMT_.100"))
    )
    (comp (ref "J7")
      (value "MOLEX_5600200220")
      (footprint "eagle-import:MOLEX_5600200220")
      (libsource (lib "eagle-import") (part "MOLEX_5600200220"))
    )
    (comp (ref "J8")
      (value "47346-0001")
      (footprint "eagle-import:MOLEX_47346")
      (fields (field (name "PART_NUM") "CON-00076"))
      (libsource (lib "eagle-import") (part "MOLEX_47346"))
    )
    (comp (ref "LED1")
      (value "BLUE")
      (footprint "eagle-import:CHIPLED_0805")
      (libsource (lib "eagle-import") (part "LEDCHIPLED_0805"))
    )
    (comp (ref "LED2")
      (value "RED")
      (footprint "eagle-import:CHIPLED_0805")
      (libsource (lib "eagle-import") (part "LEDCHIPLED_0805"))
    )
    (comp (ref "LED3")
      (value "GREEN")
      (footprint "eagle-import:CHIPLED_0805")
      (libsource (lib "eagle-import") (part "LEDCHIPLED_0805"))
    )
    (comp (ref "P1")
      (value "FTSH-105-01-L-DV-K")
      (footprint "eagle-import:SAMTEC_FTSH-105-01-L-DV-K")
      (fields (field (name "PART_NUM") "CON-00037"))
      (libsource (lib "eagle-import") (part "FTSH-105-01-L-DV-K"))
    )
    (comp (ref "R6")
      (value "10K_0603")
      (footprint "eagle-import:R0603")
      (libsource (lib "eagle-import") (part "R-US_R0603"))
    )
    (comp (ref "R7")
      (value "10K_0603")
      (footprint "eagle-import:R0603")
      (libsource (lib "eagle-import") (part "R-US_R0603"))
    )
    (comp (ref "R8")
      (value "510_Ohm_0603")
      (footprint "eagle-import:R0603")
      (libsource (lib "eagle-import") (part "R-US_R0603"))
    )
    (comp (ref "R9")
      (value "15K_0603")
      (footprint "eagle-import:R0603")
      (libsource (lib "eagle-import") (part "R-US_R0603"))
    )
    (comp (ref "R10")
      (value "NI_0603")
      (footprint "eagle-import:R0603")
      (libsource (lib "eagle-import") (part "R-US_R0603"))
    )
    (comp (ref "R11")
      (value "1K_0603")
      (footprint "eagle-import:R0603")
      (libsource (lib "eagle-import") (part "R-US_R0603"))
    )
    (comp (ref "R12")
      (value "1K_0603")
      (footprint "eagle-import:R0603")
      (libsource (lib "eagle-import") (part "R-US_R0603"))
    )
    (comp (ref "R13")
      (value "1K_0603")
      (footprint "eagle-import:R0603")
      (libsource (lib "eagle-import") (part "R-US_R0603"))
    )
    (comp (ref "R14")
      (value "22_0603")
      (footprint "eagle-import:R0603")
      (libsource (lib "eagle-import") (part "R-US_R0603"))
    )
    (comp (ref "R15")
      (value "22_0603")
      (footprint "eagle-import:R0603")
      (libsource (lib "eagle-import") (part "R-US_R0603"))
    )
    (comp (ref "R16")
      (value "CG0603MLC-05LE")
      (footprint "eagle-import:R0603")
      (libsource (lib "eagle-import") (part "R-US_R0603"))
    )
    (comp (ref "R17")
      (value "CG0603MLC-05LE")
      (footprint "eagle-import:R0603")
      (libsource (lib "eagle-import") (part "R-US_R0603"))
    )
    (comp (ref "R18")
      (value "CG0603MLC-05LE")
      (footprint "eagle-import:R0603")
      (libsource (lib "eagle-import") (part "R-US_R0603"))
    )
    (comp (ref "R19")
      (value "10K_0603")
      (footprint "eagle-import:R0603")
      (libsource (lib "eagle-import") (part "R-US_R0603"))
    )
    (comp (ref "R20")
      (value "10K_NTC_0603")
      (footprint "eagle-import:R0603")
      (libsource (lib "eagle-import") (part "R-US_R0603"))
    )
    (comp (ref "R21")
      (value "100K_0603")
      (footprint "eagle-import:R0603")
      (libsource (lib "eagle-import") (part "R-US_R0603"))
    )
    (comp (ref "R22")
      (value "100K_0603")
      (footprint "eagle-import:R0603")
      (libsource (lib "eagle-import") (part "R-US_R0603"))
    )
    (comp (ref "R23")
      (value "68K_0603")
      (footprint "eagle-import:R0603")
      (libsource (lib "eagle-import") (part "R-US_R0603"))
    )
    (comp (ref "S1")
      (value "219-4MST")
      (footprint "eagle-import:CTS-219-04")
      (libsource (lib "eagle-import") (part "219-04"))
    )
    (comp (ref "U3")
      (value "CY8C5287AXI-LP095")
      (footprint "eagle-import:TQFP100")
      (fields (field (name "PART_NUM") "ICC-00167"))
      (libsource (lib "eagle-import") (part "CYPRESS_CY8C52XX_100PIN5287"))
    )
    (comp (ref "C1")
      (value "0.1uF/100V_0603")
      (footprint "eagle-import:C0603")
      (fields (field (name "PART_NUM") "CAP-00240"))
      (libsource (lib "eagle-import") (part "0603_0.1UF_100V"))
    )
    (comp (ref "C2")
      (value "0.15uF_50V_0603")
      (footprint "eagle-import:C0603")
      (fields (field (name "PART_NUM") "CAP-00302"))
      (libsource (lib "eagle-import") (part "0603_0.15_50V"))
    )
    (comp (ref "C3")
      (value "47uF_16V_1206")
      (footprint "eagle-import:C1206")
      (fields (field (name "PART_NUM") "CAP-00301"))
      (libsource (lib "eagle-import") (part "1206_47UF_16V"))
    )
    (comp (ref "C4")
      (value "0.1uF/100V_0603")
      (footprint "eagle-import:C0603")
      (fields (field (name "PART_NUM") "CAP-00240"))
      (libsource (lib "eagle-import") (part "0603_0.1UF_100V"))
    )
    (comp (ref "D1")
      (value "RB160VA-40")
      (footprint "eagle-import:TUMD2")
      (fields (field (name "PART_NUM") "DIO-00001"))
      (libsource (lib "eagle-import") (part "ROHM_RB160VA-40"))
    )
    (comp (ref "D2")
      (value "3.3V_500mW")
      (footprint "eagle-import:SOD-123")
      (libsource (lib "eagle-import") (part "ZENERSOD-123"))
    )
    (comp (ref "D3")
      (value "RB160VA-40")
      (footprint "eagle-import:TUMD2")
      (fields (field (name "PART_NUM") "DIO-00001"))
      (libsource (lib "eagle-import") (part "ROHM_RB160VA-40"))
    )
    (comp (ref "FID1")
      (value "FIDUCIALSSMALLER")
      (footprint "eagle-import:FIDUCIAL_1MMX3MM")
      (fields (field (name "PART_NUM") "DNI-00000"))
      (libsource (lib "eagle-import") (part "FIDUCIALSSMALLER"))
    )
    (comp (ref "FID2")
      (value "FIDUCIALSSMALLER")
      (footprint "eagle-import:FIDUCIAL_1MMX3MM")
      (fields (field (name "PART_NUM") "DNI-00000"))
      (libsource (lib "eagle-import") (part "FIDUCIALSSMALLER"))
    )
    (comp (ref "FID3")
      (value "FIDUCIALSSMALLER")
      (footprint "eagle-import:FIDUCIAL_1MMX3MM")
      (fields (field (name "PART_NUM") "DNI-00000"))
      (libsource (lib "eagle-import") (part "FIDUCIALSSMALLER"))
    )
    (comp (ref "J1")
      (value "709296001004006")
      (footprint "eagle-import:AVX_709296001004006")
      (fields (field (name "PART_NUM") "CON-00273"))
      (libsource (lib "eagle-import") (part "AVX_709296001004006"))
    )
    (comp (ref "J2")
      (value "709296001004006")
      (footprint "eagle-import:AVX_709296001004006")
      (fields (field (name "PART_NUM") "CON-00273"))
      (libsource (lib "eagle-import") (part "AVX_709296001004006"))
    )
    (comp (ref "J3")
      (value "MOLEX_874370343")
      (footprint "eagle-import:MOLEX_874370343")
      (libsource (lib "eagle-import") (part "MOLEX_874370343"))
    )
    (comp (ref "J4")
      (value "MOLEX_874370343")
      (footprint "eagle-import:MOLEX_874370343")
      (libsource (lib "eagle-import") (part "MOLEX_874370343"))
    )
    (comp (ref "L1")
      (value "LPS6225-153ML")
      (footprint "eagle-import:COILCRAFT_LPS6235")
      (fields (field (name "PART_NUM") "IND-00128"))
      (libsource (lib "eagle-import") (part "COILCRAFT_LPS6225-153"))
    )
    (comp (ref "R1")
      (value "5.11K_0603")
      (footprint "eagle-import:R0603")
      (fields (field (name "PART_NUM") "RES-00263"))
      (libsource (lib "eagle-import") (part "Illum_RES_8639966_0603_5.11KΩ"))
    )
    (comp (ref "R2")
      (value "1K_0603")
      (footprint "eagle-import:R0603")
      (fields (field (name "PART_NUM") "RES-00002"))
      (libsource (lib "eagle-import") (part "Illum_RES_8639966_0603_1KΩ"))
    )
    (comp (ref "R3")
      (value "100K_0603")
      (footprint "eagle-import:R0603")
      (fields (field (name "PART_NUM") "RES-00015"))
      (libsource (lib "eagle-import") (part "Illum_RES_8639966_0603_100KΩ"))
    )
    (comp (ref "R4")
      (value "NI (121)")
      (footprint "eagle-import:R0603")
      (libsource (lib "eagle-import") (part "R-US_R0603"))
    )
    (comp (ref "R5")
      (value "100K_0603")
      (footprint "eagle-import:R0603")
      (libsource (lib "eagle-import") (part "R-US_R0603"))
    )
    (comp (ref "U1")
      (value "MP2459GJ")
      (footprint "eagle-import:TSOT_23-6")
      (fields (field (name "PART_NUM") "ICC-00074"))
      (libsource (lib "eagle-import") (part "MPS_MP2459GJ"))
    )
    (comp (ref "U2")
      (value "SN65HVD1782DR")
      (footprint "eagle-import:SO-8")
      (fields (field (name "PART_NUM") "ICC-00036"))
      (libsource (lib "eagle-import") (part "TI_SN65HVD1782DR"))
    )
    (comp (ref "Z1")
      (value "SMBJ12CA")
      (footprint "eagle-import:SMBJ")
      (libsource (lib "eagle-import") (part "TISP4360H3BJ"))
    )
    (comp (ref "Z2")
      (value "SMBJ12CA")
      (footprint "eagle-import:SMBJ")
      (libsource (lib "eagle-import") (part "TISP4360H3BJ"))
    )
    (comp (ref "Z3")
      (value "SMBJ12CA")
      (footprint "eagle-import:SMBJ")
      (libsource (lib "eagle-import") (part "TISP4360H3BJ"))
    )
    (comp (ref "C51")
      (value "1uF/100V_0805")
      (footprint "eagle-import:C0805")
      (libsource (lib "eagle-import") (part "C-EUC0805"))
    )
    (comp (ref "C52")
      (value "1uF/100V_0805")
      (footprint "eagle-import:C0805")
      (libsource (lib "eagle-import") (part "C-EUC0805"))
    )
    (comp (ref "C53")
      (value "1uF/100V_0805")
      (footprint "eagle-import:C0805")
      (libsource (lib "eagle-import") (part "C-EUC0805"))
    )
    (comp (ref "C54")
      (value "1uF/100V_0805")
      (footprint "eagle-import:C0805")
      (libsource (lib "eagle-import") (part "C-EUC0805"))
    )
    (comp (ref "C55")
      (value "0.1uF_0603")
      (footprint "eagle-import:C0603")
      (libsource (lib "eagle-import") (part "C-EUC0603"))
    )
    (comp (ref "C56")
      (value "0.1uF_0603")
      (footprint "eagle-import:C0603")
      (libsource (lib "eagle-import") (part "C-EUC0603"))
    )
    (comp (ref "C57")
      (value "1uF/100V_0805")
      (footprint "eagle-import:C0805")
      (libsource (lib "eagle-import") (part "C-EUC0805"))
    )
    (comp (ref "C58")
      (value "1uF/100V_0805")
      (footprint "eagle-import:C0805")
      (libsource (lib "eagle-import") (part "C-EUC0805"))
    )
    (comp (ref "C59")
      (value "470pF_0603")
      (footprint "eagle-import:C0603")
      (libsource (lib "eagle-import") (part "C-EUC0603"))
    )
    (comp (ref "C60")
      (value "470pF_0603")
      (footprint "eagle-import:C0603")
      (libsource (lib "eagle-import") (part "C-EUC0603"))
    )
    (comp (ref "C61")
      (value "1.0uF/16V_0603")
      (footprint "eagle-import:C0603")
      (libsource (lib "eagle-import") (part "C-EUC0603"))
    )
    (comp (ref "C62")
      (value "1.0uF/16V_0603")
      (footprint "eagle-import:C0603")
      (libsource (lib "eagle-import") (part "C-EUC0603"))
    )
    (comp (ref "C63")
      (value "4.7uF/100V_1210")
      (footprint "eagle-import:C1210")
      (libsource (lib "eagle-import") (part "C-EUC1210"))
    )
    (comp (ref "C64")
      (value "4.7uF/100V_1210")
      (footprint "eagle-import:C1210")
      (libsource (lib "eagle-import") (part "C-EUC1210"))
    )
    (comp (ref "C65")
      (value "22uF_50V_HZA226M050D16T-F")
      (footprint "eagle-import:PANASONIC_D")
      (libsource (lib "eagle-import") (part "CPOL-USD"))
    )
    (comp (ref "C66")
      (value "22uF_50V_HZA226M050D16T-F")
      (footprint "eagle-import:PANASONIC_D")
      (libsource (lib "eagle-import") (part "CPOL-USD"))
    )
    (comp (ref "D8")
      (value "MURS360T3G_SMC")
      (footprint "eagle-import:SMC")
      (libsource (lib "eagle-import") (part "SCHOTTKY-DIODESMC"))
    )
    (comp (ref "D9")
      (value "MURS360T3G_SMC")
      (footprint "eagle-import:SMC")
      (libsource (lib "eagle-import") (part "SCHOTTKY-DIODESMC"))
    )
    (comp (ref "L6")
      (value "SRP1770TA-330M_NI")
      (footprint "eagle-import:BOURNS_SRP1770TA")
      (libsource (lib "eagle-import") (part "BOURNS_SRP1770TA"))
    )
    (comp (ref "L7")
      (value "MSS1278-333ML")
      (footprint "eagle-import:MSS1260")
      (libsource (lib "eagle-import") (part "COILCRAFT_MSS1260"))
    )
    (comp (ref "L8")
      (value "SRP1770TA-330M_NI")
      (footprint "eagle-import:BOURNS_SRP1770TA")
      (libsource (lib "eagle-import") (part "BOURNS_SRP1770TA"))
    )
    (comp (ref "L9")
      (value "MSS1278-333ML")
      (footprint "eagle-import:MSS1260")
      (libsource (lib "eagle-import") (part "COILCRAFT_MSS1260"))
    )
    (comp (ref "Q5")
      (value "ZXMP10A18K")
      (footprint "eagle-import:DPAK")
      (libsource (lib "eagle-import") (part "MOSFET_P-CHANNEL_3LEADTAB_SOURCE"))
    )
    (comp (ref "Q6")
      (value "ZXMP10A18K")
      (footprint "eagle-import:DPAK")
      (libsource (lib "eagle-import") (part "MOSFET_P-CHANNEL_3LEADTAB_SOURCE"))
    )
    (comp (ref "Q7")
      (value "BSC097N06NS")
      (footprint "eagle-import:SO-8_POWERPAC")
      (libsource (lib "eagle-import") (part "SI7464DP_SO8_POWERPAC"))
    )
    (comp (ref "Q8")
      (value "BSC097N06NS")
      (footprint "eagle-import:SO-8_POWERPAC")
      (libsource (lib "eagle-import") (part "SI7464DP_SO8_POWERPAC"))
    )
    (comp (ref "R72")
      (value "62K_0603")
      (footprint "eagle-import:R0603")
      (libsource (lib "eagle-import") (part "R-US_R0603"))
    )
    (comp (ref "R73")
      (value "62K_0603")
      (footprint "eagle-import:R0603")
      (libsource (lib "eagle-import") (part "R-US_R0603"))
    )
    (comp (ref "R74")
      (value "22K_0603")
      (footprint "eagle-import:R0603")
      (libsource (lib "eagle-import") (part "R-US_R0603"))
    )
    (comp (ref "R75")
      (value "22K_0603")
      (footprint "eagle-import:R0603")
      (libsource (lib "eagle-import") (part "R-US_R0603"))
    )
    (comp (ref "R76")
      (value "100K_0603")
      (footprint "eagle-import:R0603")
      (libsource (lib "eagle-import") (part "R-US_R0603"))
    )
    (comp (ref "R77")
      (value "100K_0603")
      (footprint "eagle-import:R0603")
      (libsource (lib "eagle-import") (part "R-US_R0603"))
    )
    (comp (ref "R78")
      (value "6.98K_0603")
      (footprint "eagle-import:R0603")
      (libsource (lib "eagle-import") (part "R-US_R0603"))
    )
    (comp (ref "R79")
      (value "6.98K_0603")
      (footprint "eagle-import:R0603")
      (libsource (lib "eagle-import") (part "R-US_R0603"))
    )
    (comp (ref "R80")
      (value "49.9K_0603")
      (footprint "eagle-import:R0603")
      (libsource (lib "eagle-import") (part "R-US_R0603"))
    )
    (comp (ref "R81")
      (value "49.9K_0603")
      (footprint "eagle-import:R0603")
      (libsource (lib "eagle-import") (part "R-US_R0603"))
    )
    (comp (ref "R82")
      (value "NI_0603")
      (footprint "eagle-import:R0603")
      (libsource (lib "eagle-import") (part "R-US_R0603"))
    )
    (comp (ref "R83")
      (value "16.5K_0603")
      (footprint "eagle-import:R0603")
      (libsource (lib "eagle-import") (part "R-US_R0603"))
    )
    (comp (ref "R84")
      (value "NI_0603")
      (footprint "eagle-import:R0603")
      (libsource (lib "eagle-import") (part "R-US_R0603"))
    )
    (comp (ref "R85")
      (value "16.5K_0603")
      (footprint "eagle-import:R0603")
      (libsource (lib "eagle-import") (part "R-US_R0603"))
    )
    (comp (ref "R86")
      (value "10_0603")
      (footprint "eagle-import:R0603")
      (libsource (lib "eagle-import") (part "R-US_R0603"))
    )
    (comp (ref "R87")
      (value "10_0603")
      (footprint "eagle-import:R0603")
      (libsource (lib "eagle-import") (part "R-US_R0603"))
    )
    (comp (ref "R88")
      (value "0.083_OHM_2512")
      (footprint "eagle-import:R2512")
      (libsource (lib "eagle-import") (part "R-US_R2512"))
    )
    (comp (ref "R89")
      (value "0.083_OHM_2512")
      (footprint "eagle-import:R2512")
      (libsource (lib "eagle-import") (part "R-US_R2512"))
    )
    (comp (ref "R90")
      (value "10_0603")
      (footprint "eagle-import:R0603")
      (libsource (lib "eagle-import") (part "R-US_R0603"))
    )
    (comp (ref "R91")
      (value "10_0603")
      (footprint "eagle-import:R0603")
      (libsource (lib "eagle-import") (part "R-US_R0603"))
    )
    (comp (ref "R92")
      (value "10K_0603")
      (footprint "eagle-import:R0603")
      (libsource (lib "eagle-import") (part "R-US_R0603"))
    )
    (comp (ref "R93")
      (value "10K_0603")
      (footprint "eagle-import:R0603")
      (libsource (lib "eagle-import") (part "R-US_R0603"))
    )
    (comp (ref "U6")
      (value "LM3409HVMY/NOPB")
      (footprint "eagle-import:MSOP10-THERMALENHANCED")
      (libsource (lib "eagle-import") (part "LM3409HV"))
    )
    (comp (ref "U7")
      (value "LM3409HVMY/NOPB")
      (footprint "eagle-import:MSOP10-THERMALENHANCED")
      (libsource (lib "eagle-import") (part "LM3409HV"))
    )
    (comp (ref "ZD3")
      (value "NI_SOD523")
      (footprint "eagle-import:SOD-523")
      (libsource (lib "eagle-import") (part "ZENER_SOD-523"))
    )
    (comp (ref "ZD4")
      (value "NI_SOD523")
      (footprint "eagle-import:SOD-523")
      (libsource (lib "eagle-import") (part "ZENER_SOD-523"))
    )
  )
  (nets
    (net (code "1") (name "+5V") (class "Default")
      (node (ref "C12") (pin "2") (pinfunction "2_2") (pintype "passive"))
      (node (ref "C13") (pin "2") (pinfunction "2_2") (pintype "passive"))
      (node (ref "C14") (pin "2") (pinfunction "2_2") (pintype "passive"))
      (node (ref "C16") (pin "2") (pinfunction "2_2") (pintype "passive"))
      (node (ref "C17") (pin "1") (pinfunction "1_1") (pintype "passive"))
      (node (ref "C22") (pin "1") (pinfunction "1_1") (pintype "passive"))
      (node (ref "C26") (pin "2") (pinfunction "2_2") (pintype "passive"))
      (node (ref "C3") (pin "1") (pinfunction "1_1") (pintype "passive"))
      (node (ref "C30") (pin "1") (pinfunction "1_1") (pintype "passive"))
      (node (ref "C34") (pin "2") (pinfunction "2_2") (pintype "passive"))
      (node (ref "C4") (pin "1") (pinfunction "1_1") (pintype "passive"))
      (node (ref "C5") (pin "2") (pinfunction "2_2") (pintype "passive"))
      (node (ref "C6") (pin "2") (pinfunction "2_2") (pintype "passive"))
      (node (ref "C7") (pin "2") (pinfunction "2_2") (pintype "passive"))
      (node (ref "C8") (pin "2") (pinfunction "2_2") (pintype "passive"))
      (node (ref "C9") (pin "2") (pinfunction "2_2") (pintype "passive"))
      (node (ref "D5") (pin "C") (pinfunction "C_C") (pintype "passive"))
      (node (ref "IC1") (pin "4") (pinfunction "V+_4") (pintype "power_in"))
      (node (ref "IC2") (pin "4") (pinfunction "V+_4") (pintype "power_in"))
      (node (ref "J6") (pin "1") (pinfunction "1_1") (pintype "bidirectional"))
      (node (ref "L1") (pin "2") (pinfunction "2_2") (pintype "passive"))
      (node (ref "P1") (pin "1") (pinfunction "1_1") (pintype "bidirectional"))
      (node (ref "R1") (pin "2") (pinfunction "2_2") (pintype "passive"))
      (node (ref "R114") (pin "1") (pinfunction "1_1") (pintype "passive"))
      (node (ref "R115") (pin "1") (pinfunction "1_1") (pintype "passive"))
      (node (ref "R19") (pin "1") (pinfunction "1_1") (pintype "passive"))
      (node (ref "R6") (pin "2") (pinfunction "2_2") (pintype "passive"))
      (node (ref "R7") (pin "1") (pinfunction "1_1") (pintype "passive"))
      (node (ref "R70") (pin "1") (pinfunction "1_1") (pintype "passive"))
      (node (ref "R71") (pin "1") (pinfunction "1_1") (pintype "passive"))
      (node (ref "R9") (pin "2") (pinfunction "2_2") (pintype "passive"))
      (node (ref "R92") (pin "1") (pinfunction "1_1") (pintype "passive"))
      (node (ref "R93") (pin "1") (pinfunction "1_1") (pintype "passive"))
      (node (ref "U2") (pin "8") (pinfunction "VCC_8") (pintype "bidirectional"))
      (node (ref "U3") (pin "100") (pinfunction "VDDIO2_100") (pintype "bidirectional"))
      (node (ref "U3") (pin "26") (pinfunction "VDDIO1_26") (pintype "bidirectional"))
      (node (ref "U3") (pin "37") (pinfunction "VDDD_37") (pintype "bidirectional"))
      (node (ref "U3") (pin "50") (pinfunction "VDDIO3_50") (pintype "bidirectional"))
      (node (ref "U3") (pin "65") (pinfunction "VDDA_65") (pintype "bidirectional"))
      (node (ref "U3") (pin "75") (pinfunction "VDDIO_75") (pintype "bidirectional"))
      (node (ref "U3") (pin "88") (pinfunction "VDDD_88") (pintype "bidirectional"))
    )
    (net (code "2") (name "ADIM1") (class "Default")
      (node (ref "R37") (pin "2") (pinfunction "2_2") (pintype "passive"))
      (node (ref "U3") (pin "24") (pinfunction "P1(4)-TDI_24") (pintype "bidirectional"))
    )
    (net (code "3") (name "ADIM2") (class "Default")
      (node (ref "R38") (pin "2") (pinfunction "2_2") (pintype "passive"))
      (node (ref "U3") (pin "22") (pinfunction "P1(2)_22") (pintype "bidirectional"))
    )
    (net (code "4") (name "ADIM3") (class "Default")
      (node (ref "R26") (pin "2") (pinfunction "2_2") (pintype "passive"))
      (node (ref "U3") (pin "69") (pinfunction "P4(0)_69") (pintype "bidirectional"))
    )
    (net (code "5") (name "ADIM4") (class "Default")
      (node (ref "R36") (pin "2") (pinfunction "2_2") (pintype "passive"))
      (node (ref "U3") (pin "6") (pinfunction "P6(4)_6") (pintype "bidirectional"))
    )
    (net (code "6") (name "ADIM5") (class "Default")
      (node (ref "R25") (pin "2") (pinfunction "2_2") (pintype "passive"))
      (node (ref "U3") (pin "73") (pinfunction "P0(2)_73") (pintype "bidirectional"))
    )
    (net (code "7") (name "ADIM6") (class "Default")
      (node (ref "R24") (pin "2") (pinfunction "2_2") (pintype "passive"))
      (node (ref "U3") (pin "72") (pinfunction "P0(1)_72") (pintype "bidirectional"))
    )
    (net (code "8") (name "ANODE1") (class "Default")
      (node (ref "C48") (pin "2") (pinfunction "2_2") (pintype "passive"))
      (node (ref "C50") (pin "+") (pinfunction "+_+") (pintype "passive"))
      (node (ref "J10") (pin "11") (pinfunction "11_11") (pintype "bidirectional"))
      (node (ref "J9") (pin "11") (pinfunction "11_11") (pintype "bidirectional"))
      (node (ref "L4") (pin "P$2") (pinfunction "2_P$2") (pintype "passive"))
      (node (ref "L5") (pin "2") (pinfunction "2_2") (pintype "passive"))
      (node (ref "Q4") (pin "5") (pinfunction "D_5") (pintype "passive"))
      (node (ref "Q4") (pin "6") (pinfunction "D1_6") (pintype "passive"))
      (node (ref "Q4") (pin "7") (pinfunction "D2_7") (pintype "passive"))
      (node (ref "Q4") (pin "8") (pinfunction "D3_8") (pintype "passive"))
      (node (ref "Q4") (pin "9") (pinfunction "D4_9") (pintype "passive"))
      (node (ref "R63") (pin "1") (pinfunction "1_1") (pintype "passive"))
    )
    (net (code "9") (name "ANODE2") (class "Default")
      (node (ref "C47") (pin "2") (pinfunction "2_2") (pintype "passive"))
      (node (ref "C49") (pin "+") (pinfunction "+_+") (pintype "passive"))
      (node (ref "J10") (pin "12") (pinfunction "12_12") (pintype "bidirectional"))
      (node (ref "J9") (pin "12") (pinfunction "12_12") (pintype "bidirectional"))
      (node (ref "L2") (pin "P$2") (pinfunction "2_P$2") (pintype "passive"))
      (node (ref "L3") (pin "2") (pinfunction "2_2") (pintype "passive"))
      (node (ref "Q3") (pin "5") (pinfunction "D_5") (pintype "passive"))
      (node (ref "Q3") (pin "6") (pinfunction "D1_6") (pintype "passive"))
      (node (ref "Q3") (pin "7") (pinfunction "D2_7") (pintype "passive"))
      (node (ref "Q3") (pin "8") (pinfunction "D3_8") (pintype "passive"))
      (node (ref "Q3") (pin "9") (pinfunction "D4_9") (pintype "passive"))
      (node (ref "R61") (pin "1") (pinfunction "1_1") (pintype "passive"))
    )
    (net (code "10") (name "ANODE3") (class "Default")
      (node (ref "C64") (pin "2") (pinfunction "2_2") (pintype "passive"))
      (node (ref "C66") (pin "+") (pinfunction "+_+") (pintype "passive"))
      (node (ref "J10") (pin "9") (pinfunction "9_9") (pintype "bidirectional"))
      (node (ref "J9") (pin "9") (pinfunction "9_9") (pintype "bidirectional"))
      (node (ref "L8") (pin "P$2") (pinfunction "2_P$2") (pintype "passive"))
      (node (ref "L9") (pin "2") (pinfunction "2_2") (pintype "passive"))
      (node (ref "Q8") (pin "5") (pinfunction "D_5") (pintype "passive"))
      (node (ref "Q8") (pin "6") (pinfunction "D1_6") (pintype "passive"))
      (node (ref "Q8") (pin "7") (pinfunction "D2_7") (pintype "passive"))
      (node (ref "Q8") (pin "8") (pinfunction "D3_8") (pintype "passive"))
      (node (ref "Q8") (pin "9") (pinfunction "D4_9") (pintype "passive"))
      (node (ref "R85") (pin "1") (pinfunction "1_1") (pintype "passive"))
    )
    (net (code "11") (name "ANODE4") (class "Default")
      (node (ref "C63") (pin "2") (pinfunction "2_2") (pintype "passive"))
      (node (ref "C65") (pin "+") (pinfunction "+_+") (pintype "passive"))
      (node (ref "J10") (pin "10") (pinfunction "10_10") (pintype "bidirectional"))
      (node (ref "J9") (pin "10") (pinfunction "10_10") (pintype "bidirectional"))
      (node (ref "L6") (pin "P$2") (pinfunction "2_P$2") (pintype "passive"))
      (node (ref "L7") (pin "2") (pinfunction "2_2") (pintype "passive"))
      (node (ref "Q7") (pin "5") (pinfunction "D_5") (pintype "passive"))
      (node (ref "Q7") (pin "6") (pinfunction "D1_6") (pintype "passive"))
      (node (ref "Q7") (pin "7") (pinfunction "D2_7") (pintype "passive"))
      (node (ref "Q7") (pin "8") (pinfunction "D3_8") (pintype "passive"))
      (node (ref "Q7") (pin "9") (pinfunction "D4_9") (pintype "passive"))
      (node (ref "R83") (pin "1") (pinfunction "1_1") (pintype "passive"))
    )
    (net (code "12") (name "ANODE5") (class "Default")
      (node (ref "C79") (pin "2") (pinfunction "2_2") (pintype "passive"))
      (node (ref "C81") (pin "+") (pinfunction "+_+") (pintype "passive"))
      (node (ref "J10") (pin "7") (pinfunction "7_7") (pintype "bidirectional"))
      (node (ref "J9") (pin "7") (pinfunction "7_7") (pintype "bidirectional"))
      (node (ref "L10") (pin "P$2") (pinfunction "2_P$2") (pintype "passive"))
      (node (ref "L11") (pin "2") (pinfunction "2_2") (pintype "passive"))
      (node (ref "Q11") (pin "5") (pinfunction "D_5") (pintype "passive"))
      (node (ref "Q11") (pin "6") (pinfunction "D1_6") (pintype "passive"))
      (node (ref "Q11") (pin "7") (pinfunction "D2_7") (pintype "passive"))
      (node (ref "Q11") (pin "8") (pinfunction "D3_8") (pintype "passive"))
      (node (ref "Q11") (pin "9") (pinfunction "D4_9") (pintype "passive"))
      (node (ref "R105") (pin "1") (pinfunction "1_1") (pintype "passive"))
    )
    (net (code "13") (name "ANODE6") (class "Default")
      (node (ref "C80") (pin "2") (pinfunction "2_2") (pintype "passive"))
      (node (ref "C82") (pin "+") (pinfunction "+_+") (pintype "passive"))
      (node (ref "J10") (pin "1") (pinfunction "1_1") (pintype "bidirectional"))
      (node (ref "J9") (pin "1") (pinfunction "1_1") (pintype "bidirectional"))
      (node (ref "L12") (pin "P$2") (pinfunction "2_P$2") (pintype "passive"))
      (node (ref "L13") (pin "2") (pinfunction "2_2") (pintype "passive"))
      (node (ref "Q12") (pin "5") (pinfunction "D_5") (pintype "passive"))
      (node (ref "Q12") (pin "6") (pinfunction "D1_6") (pintype "passive"))
      (node (ref "Q12") (pin "7") (pinfunction "D2_7") (pintype "passive"))
      (node (ref "Q12") (pin "8") (pinfunction "D3_8") (pintype "passive"))
      (node (ref "Q12") (pin "9") (pinfunction "D4_9") (pintype "passive"))
      (node (ref "R107") (pin "1") (pinfunction "1_1") (pintype "passive"))
    )
    (net (code "14") (name "DMX+_IN") (class "Default")
      (node (ref "J3") (pin "1") (pinfunction "1_1") (pintype "bidirectional"))
      (node (ref "J4") (pin "1") (pinfunction "1_1") (pintype "bidirectional"))
      (node (ref "R4") (pin "2") (pinfunction "2_2") (pintype "passive"))
      (node (ref "U2") (pin "6") (pinfunction "A_6") (pintype "bidirectional"))
      (node (ref "Z2") (pin "1") (pinfunction "R_1") (pintype "bidirectional"))
      (node (ref "Z3") (pin "2") (pinfunction "T_2") (pintype "bidirectional"))
    )
    (net (code "15") (name "DMX-_IN") (class "Default")
      (node (ref "J3") (pin "2") (pinfunction "2_2") (pintype "bidirectional"))
      (node (ref "J4") (pin "2") (pinfunction "2_2") (pintype "bidirectional"))
      (node (ref "R4") (pin "1") (pinfunction "1_1") (pintype "passive"))
      (node (ref "U2") (pin "7") (pinfunction "B_7") (pintype "bidirectional"))
      (node (ref "Z1") (pin "1") (pinfunction "R_1") (pintype "bidirectional"))
      (node (ref "Z2") (pin "2") (pinfunction "T_2") (pintype "bidirectional"))
    )
    (net (code "16") (name "DMXDIR") (class "Default")
      (node (ref "R5") (pin "2") (pinfunction "2_2") (pintype "passive"))
      (node (ref "U2") (pin "2") (pinfunction "/RE_2") (pintype "bidirectional"))
      (node (ref "U2") (pin "3") (pinfunction "DE_3") (pintype "bidirectional"))
      (node (ref "U3") (pin "55") (pinfunction "KHZXXTALO-P15(2)_55") (pintype "bidirectional"))
    )
    (net (code "17") (name "EXT_TEMPSENSE1") (class "Default")
      (node (ref "D4") (pin "C") (pinfunction "C_C") (pintype "passive"))
      (node (ref "J7") (pin "1") (pinfunction "1_1") (pintype "bidirectional"))
      (node (ref "R10") (pin "2") (pinfunction "2_2") (pintype "passive"))
      (node (ref "R8") (pin "1") (pinfunction "1_1") (pintype "passive"))
      (node (ref "R9") (pin "1") (pinfunction "1_1") (pintype "passive"))
    )
    (net (code "18") (name "GND") (class "Default")
      (node (ref "C1") (pin "2") (pinfunction "2_2") (pintype "passive"))
      (node (ref "C10") (pin "1") (pinfunction "1_1") (pintype "passive"))
      (node (ref "C11") (pin "1") (pinfunction "1_1") (pintype "passive"))
      (node (ref "C12") (pin "1") (pinfunction "1_1") (pintype "passive"))
      (node (ref "C13") (pin "1") (pinfunction "1_1") (pintype "passive"))
      (node (ref "C14") (pin "1") (pinfunction "1_1") (pintype "passive"))
      (node (ref "C15") (pin "1") (pinfunction "1_1") (pintype "passive"))
      (node (ref "C16") (pin "1") (pinfunction "1_1") (pintype "passive"))
      (node (ref "C17") (pin "2") (pinfunction "2_2") (pintype "passive"))
      (node (ref "C18") (pin "2") (pinfunction "2_2") (pintype "passive"))
      (node (ref "C19") (pin "1") (pinfunction "1_1") (pintype "passive"))
      (node (ref "C20") (pin "1") (pinfunction "1_1") (pintype "passive"))
      (node (ref "C21") (pin "1") (pinfunction "1_1") (pintype "passive"))
      (node (ref "C22") (pin "2") (pinfunction "2_2") (pintype "passive"))
      (node (ref "C26") (pin "1") (pinfunction "1_1") (pintype "passive"))
      (node (ref "C27") (pin "1") (pinfunction "1_1") (pintype "passive"))
      (node (ref "C28") (pin "1") (pinfunction "1_1") (pintype "passive"))
      (node (ref "C29") (pin "1") (pinfunction "1_1") (pintype "passive"))
      (node (ref "C3") (pin "2") (pinfunction "2_2") (pintype "passive"))
      (node (ref "C30") (pin "2") (pinfunction "2_2") (pintype "passive"))
      (node (ref "C34") (pin "1") (pinfunction "1_1") (pintype "passive"))
      (node (ref "C35") (pin "2") (pinfunction "2_2") (pintype "passive"))
      (node (ref "C36") (pin "2") (pinfunction "2_2") (pintype "passive"))
      (node (ref "C37") (pin "2") (pinfunction "2_2") (pintype "passive"))
      (node (ref "C38") (pin "2") (pinfunction "2_2") (pintype "passive"))
      (node (ref "C39") (pin "1") (pinfunction "1_1") (pintype "passive"))
      (node (ref "C4") (pin "2") (pinfunction "2_2") (pintype "passive"))
      (node (ref "C40") (pin "1") (pinfunction "1_1") (pintype "passive"))
      (node (ref "C41") (pin "2") (pinfunction "2_2") (pintype "passive"))
      (node (ref "C42") (pin "2") (pinfunction "2_2") (pintype "passive"))
      (node (ref "C43") (pin "1") (pinfunction "1_1") (pintype "passive"))
      (node (ref "C44") (pin "1") (pinfunction "1_1") (pintype "passive"))
      (node (ref "C47") (pin "1") (pinfunction "1_1") (pintype "passive"))
      (node (ref "C48") (pin "1") (pinfunction "1_1") (pintype "passive"))
      (node (ref "C49") (pin "-") (pinfunction "-_-") (pintype "passive"))
      (node (ref "C5") (pin "1") (pinfunction "1_1") (pintype "passive"))
      (node (ref "C50") (pin "-") (pinfunction "-_-") (pintype "passive"))
      (node (ref "C51") (pin "2") (pinfunction "2_2") (pintype "passive"))
      (node (ref "C52") (pin "2") (pinfunction "2_2") (pintype "passive"))
      (node (ref "C53") (pin "2") (pinfunction "2_2") (pintype "passive"))
      (node (ref "C54") (pin "2") (pinfunction "2_2") (pintype "passive"))
      (node (ref "C55") (pin "1") (pinfunction "1_1") (pintype "passive"))
      (node (ref "C56") (pin "1") (pinfunction "1_1") (pintype "passive"))
      (node (ref "C57") (pin "2") (pinfunction "2_2") (pintype "passive"))
      (node (ref "C58") (pin "2") (pinfunction "2_2") (pintype "passive"))
      (node (ref "C59") (pin "1") (pinfunction "1_1") (pintype "passive"))
      (node (ref "C6") (pin "1") (pinfunction "1_1") (pintype "passive"))
      (node (ref "C60") (pin "1") (pinfunction "1_1") (pintype "passive"))
      (node (ref "C63") (pin "1") (pinfunction "1_1") (pintype "passive"))
      (node (ref "C64") (pin "1") (pinfunction "1_1") (pintype "passive"))
      (node (ref "C65") (pin "-") (pinfunction "-_-") (pintype "passive"))
      (node (ref "C66") (pin "-") (pinfunction "-_-") (pintype "passive"))
      (node (ref "C67") (pin "2") (pinfunction "2_2") (pintype "passive"))
      (node (ref "C68") (pin "2") (pinfunction "2_2") (pintype "passive"))
      (node (ref "C69") (pin "2") (pinfunction "2_2") (pintype "passive"))
      (node (ref "C7") (pin "1") (pinfunction "1_1") (pintype "passive"))
      (node (ref "C70") (pin "2") (pinfunction "2_2") (pintype "passive"))
      (node (ref "C71") (pin "1") (pinfunction "1_1") (pintype "passive"))
      (node (ref "C72") (pin "1") (pinfunction "1_1") (pintype "passive"))
      (node (ref "C73") (pin "2") (pinfunction "2_2") (pintype "passive"))
      (node (ref "C74") (pin "2") (pinfunction "2_2") (pintype "passive"))
      (node (ref "C75") (pin "1") (pinfunction "1_1") (pintype "passive"))
      (node (ref "C76") (pin "1") (pinfunction "1_1") (pintype "passive"))
      (node (ref "C79") (pin "1") (pinfunction "1_1") (pintype "passive"))
      (node (ref "C8") (pin "1") (pinfunction "1_1") (pintype "passive"))
      (node (ref "C80") (pin "1") (pinfunction "1_1") (pintype "passive"))
      (node (ref "C81") (pin "-") (pinfunction "-_-") (pintype "passive"))
      (node (ref "C82") (pin "-") (pinfunction "-_-") (pintype "passive"))
      (node (ref "C9") (pin "1") (pinfunction "1_1") (pintype "passive"))
      (node (ref "D10") (pin "A") (pinfunction "A_A") (pintype "passive"))
      (node (ref "D11") (pin "A") (pinfunction "A_A") (pintype "passive"))
      (node (ref "D2") (pin "A") (pinfunction "A_A") (pintype "passive"))
      (node (ref "D3") (pin "A") (pinfunction "A_A") (pintype "passive"))
      (node (ref "D4") (pin "A") (pinfunction "A_A") (pintype "passive"))
      (node (ref "D6") (pin "A") (pinfunction "A_A") (pintype "passive"))
      (node (ref "D7") (pin "A") (pinfunction "A_A") (pintype "passive"))
      (node (ref "D8") (pin "A") (pinfunction "A_A") (pintype "passive"))
      (node (ref "D9") (pin "A") (pinfunction "A_A") (pintype "passive"))
      (node (ref "IC1") (pin "11") (pinfunction "V-_11") (pintype "power_in"))
      (node (ref "IC2") (pin "11") (pinfunction "V-_11") (pintype "power_in"))
      (node (ref "J10") (pin "3") (pinfunction "3_3") (pintype "bidirectional"))
      (node (ref "J10") (pin "4") (pinfunction "4_4") (pintype "bidirectional"))
      (node (ref "J10") (pin "5") (pinfunction "5_5") (pintype "bidirectional"))
      (node (ref "J10") (pin "6") (pinfunction "6_6") (pintype "bidirectional"))
      (node (ref "J10") (pin "8") (pinfunction "8_8") (pintype "bidirectional"))
      (node (ref "J2") (pin "1") (pinfunction "1_1") (pintype "bidirectional"))
      (node (ref "J3") (pin "3") (pinfunction "3_3") (pintype "bidirectional"))
      (node (ref "J4") (pin "3") (pinfunction "3_3") (pintype "bidirectional"))
      (node (ref "J5") (pin "3") (pinfunction "3_3") (pintype "bidirectional"))
      (node (ref "J6") (pin "2") (pinfunction "2_2") (pintype "bidirectional"))
      (node (ref "J7") (pin "2") (pinfunction "2_2") (pintype "bidirectional"))
      (node (ref "J8") (pin "GND") (pinfunction "GND_GND") (pintype "bidirectional"))
      (node (ref "J9") (pin "3") (pinfunction "3_3") (pintype "bidirectional"))
      (node (ref "J9") (pin "4") (pinfunction "4_4") (pintype "bidirectional"))
      (node (ref "J9") (pin "5") (pinfunction "5_5") (pintype "bidirectional"))
      (node (ref "J9") (pin "6") (pinfunction "6_6") (pintype "bidirectional"))
      (node (ref "J9") (pin "8") (pinfunction "8_8") (pintype "bidirectional"))
      (node (ref "LED1") (pin "C") (pinfunction "C_C") (pintype "passive"))
      (node (ref "LED2") (pin "C") (pinfunction "C_C") (pintype "passive"))
      (node (ref "LED3") (pin "C") (pinfunction "C_C") (pintype "passive"))
      (node (ref "P1") (pin "3") (pinfunction "3_3") (pintype "bidirectional"))
      (node (ref "P1") (pin "5") (pinfunction "5_5") (pintype "bidirectional"))
      (node (ref "P1") (pin "7") (pinfunction "7_7") (pintype "bidirectional"))
      (node (ref "P1") (pin "9") (pinfunction "9_9") (pintype "bidirectional"))
      (node (ref "Q11") (pin "1") (pinfunction "S_1") (pintype "passive"))
      (node (ref "Q11") (pin "2") (pinfunction "S1_2") (pintype "passive"))
      (node (ref "Q11") (pin "3") (pinfunction "S2_3") (pintype "passive"))
      (node (ref "Q12") (pin "1") (pinfunction "S_1") (pintype "passive"))
      (node (ref "Q12") (pin "2") (pinfunction "S1_2") (pintype "passive"))
      (node (ref "Q12") (pin "3") (pinfunction "S2_3") (pintype "passive"))
      (node (ref "Q3") (pin "1") (pinfunction "S_1") (pintype "passive"))
      (node (ref "Q3") (pin "2") (pinfunction "S1_2") (pintype "passive"))
      (node (ref "Q3") (pin "3") (pinfunction "S2_3") (pintype "passive"))
      (node (ref "Q4") (pin "1") (pinfunction "S_1") (pintype "passive"))
      (node (ref "Q4") (pin "2") (pinfunction "S1_2") (pintype "passive"))
      (node (ref "Q4") (pin "3") (pinfunction "S2_3") (pintype "passive"))
      (node (ref "Q7") (pin "1") (pinfunction "S_1") (pintype "passive"))
      (node (ref "Q7") (pin "2") (pinfunction "S1_2") (pintype "passive"))
      (node (ref "Q7") (pin "3") (pinfunction "S2_3") (pintype "passive"))
      (node (ref "Q8") (pin "1") (pinfunction "S_1") (pintype "passive"))
      (node (ref "Q8") (pin "2") (pinfunction "S1_2") (pintype "passive"))
      (node (ref "Q8") (pin "3") (pinfunction "S2_3") (pintype "passive"))
      (node (ref "R10") (pin "1") (pinfunction "1_1") (pintype "passive"))
      (node (ref "R100") (pin "1") (pinfunction "1_1") (pintype "passive"))
      (node (ref "R101") (pin "1") (pinfunction "1_1") (pintype "passive"))
      (node (ref "R16") (pin "2") (pinfunction "2_2") (pintype "passive"))
      (node (ref "R17") (pin "2") (pinfunction "2_2") (pintype "passive"))
      (node (ref "R18") (pin "2") (pinfunction "2_2") (pintype "passive"))
      (node (ref "R2") (pin "1") (pinfunction "1_1") (pintype "passive"))
      (node (ref "R20") (pin "2") (pinfunction "2_2") (pintype "passive"))
      (node (ref "R21") (pin "1") (pinfunction "1_1") (pintype "passive"))
      (node (ref "R23") (pin "1") (pinfunction "1_1") (pintype "passive"))
      (node (ref "R33") (pin "1") (pinfunction "1_1") (pintype "passive"))
      (node (ref "R34") (pin "1") (pinfunction "1_1") (pintype "passive"))
      (node (ref "R35") (pin "1") (pinfunction "1_1") (pintype "passive"))
      (node (ref "R45") (pin "1") (pinfunction "1_1") (pintype "passive"))
      (node (ref "R46") (pin "1") (pinfunction "1_1") (pintype "passive"))
      (node (ref "R47") (pin "1") (pinfunction "1_1") (pintype "passive"))
      (node (ref "R5") (pin "1") (pinfunction "1_1") (pintype "passive"))
      (node (ref "R52") (pin "1") (pinfunction "1_1") (pintype "passive"))
      (node (ref "R53") (pin "1") (pinfunction "1_1") (pintype "passive"))
      (node (ref "R54") (pin "1") (pinfunction "1_1") (pintype "passive"))
      (node (ref "R55") (pin "1") (pinfunction "1_1") (pintype "passive"))
      (node (ref "R56") (pin "1") (pinfunction "1_1") (pintype "passive"))
      (node (ref "R57") (pin "1") (pinfunction "1_1") (pintype "passive"))
      (node (ref "R74") (pin "1") (pinfunction "1_1") (pintype "passive"))
      (node (ref "R75") (pin "1") (pinfunction "1_1") (pintype "passive"))
      (node (ref "R76") (pin "1") (pinfunction "1_1") (pintype "passive"))
      (node (ref "R77") (pin "1") (pinfunction "1_1") (pintype "passive"))
      (node (ref "R78") (pin "1") (pinfunction "1_1") (pintype "passive"))
      (node (ref "R79") (pin "1") (pinfunction "1_1") (pintype "passive"))
      (node (ref "R96") (pin "1") (pinfunction "1_1") (pintype "passive"))
      (node (ref "R97") (pin "1") (pinfunction "1_1") (pintype "passive"))
      (node (ref "R98") (pin "1") (pinfunction "1_1") (pintype "passive"))
      (node (ref "R99") (pin "1") (pinfunction "1_1") (pintype "passive"))
      (node (ref "S1") (pin "1") (pinfunction "1_1") (pintype "passive"))
      (node (ref "S1") (pin "2") (pinfunction "2_2") (pintype "passive"))
      (node (ref "S1") (pin "3") (pinfunction "3_3") (pintype "passive"))
      (node (ref "S1") (pin "4") (pinfunction "4_4") (pintype "passive"))
      (node (ref "U1") (pin "2") (pinfunction "GND_2") (pintype "bidirectional"))
      (node (ref "U2") (pin "5") (pinfunction "GND_5") (pintype "bidirectional"))
      (node (ref "U3") (pin "10") (pinfunction "VSSB_10") (pintype "bidirectional"))
      (node (ref "U3") (pin "12") (pinfunction "VBOOST_12") (pintype "bidirectional"))
      (node (ref "U3") (pin "13") (pinfunction "VBAT_13") (pintype "bidirectional"))
      (node (ref "U3") (pin "14") (pinfunction "VSSD_14") (pintype "bidirectional"))
      (node (ref "U3") (pin "38") (pinfunction "VSSD_38") (pintype "bidirectional"))
      (node (ref "U3") (pin "64") (pinfunction "VSSA_64") (pintype "bidirectional"))
      (node (ref "U3") (pin "66") (pinfunction "VSSD_66") (pintype "bidirectional"))
      (node (ref "U3") (pin "87") (pinfunction "VSSD_87") (pintype "bidirectional"))
      (node (ref "U4") (pin "5") (pinfunction "GND_5") (pintype "bidirectional"))
      (node (ref "U4") (pin "THERM") (pinfunction "THERM_THERM") (pintype "bidirectional"))
      (node (ref "U5") (pin "5") (pinfunction "GND_5") (pintype "bidirectional"))
      (node (ref "U5") (pin "THERM") (pinfunction "THERM_THERM") (pintype "bidirectional"))
      (node (ref "U6") (pin "5") (pinfunction "GND_5") (pintype "bidirectional"))
      (node (ref "U6") (pin "THERM") (pinfunction "THERM_THERM") (pintype "bidirectional"))
      (node (ref "U7") (pin "5") (pinfunction "GND_5") (pintype "bidirectional"))
      (node (ref "U7") (pin "THERM") (pinfunction "THERM_THERM") (pintype "bidirectional"))
      (node (ref "U8") (pin "5") (pinfunction "GND_5") (pintype "bidirectional"))
      (node (ref "U8") (pin "THERM") (pinfunction "THERM_THERM") (pintype "bidirectional"))
      (node (ref "U9") (pin "5") (pinfunction "GND_5") (pintype "bidirectional"))
      (node (ref "U9") (pin "THERM") (pinfunction "THERM_THERM") (pintype "bidirectional"))
      (node (ref "Z1") (pin "2") (pinfunction "T_2") (pintype "bidirectional"))
      (node (ref "Z3") (pin "1") (pinfunction "R_1") (pintype "bidirectional"))
    )
    (net (code "19") (name "LED_BLUE") (class "Default")
      (node (ref "R11") (pin "2") (pinfunction "2_2") (pintype "passive"))
      (node (ref "U3") (pin "27") (pinfunction "P1(6)_27") (pintype "bidirectional"))
    )
    (net (code "20") (name "LED_GREEN") (class "Default")
      (node (ref "R13") (pin "2") (pinfunction "2_2") (pintype "passive"))
      (node (ref "U3") (pin "29") (pinfunction "P12(6)_29") (pintype "bidirectional"))
    )
    (net (code "21") (name "LED_RED") (class "Default")
      (node (ref "R12") (pin "2") (pinfunction "2_2") (pintype "passive"))
      (node (ref "U3") (pin "28") (pinfunction "P1(7)_28") (pintype "bidirectional"))
    )
    (net (code "22") (name "LPCTRL1") (class "Default")
      (node (ref "R43") (pin "2") (pinfunction "2_2") (pintype "passive"))
      (node (ref "R46") (pin "2") (pinfunction "2_2") (pintype "passive"))
      (node (ref "R50") (pin "1") (pinfunction "1_1") (pintype "passive"))
    )
    (net (code "23") (name "LPCTRL2") (class "Default")
      (node (ref "R44") (pin "2") (pinfunction "2_2") (pintype "passive"))
      (node (ref "R47") (pin "2") (pinfunction "2_2") (pintype "passive"))
      (node (ref "R49") (pin "1") (pinfunction "1_1") (pintype "passive"))
    )
    (net (code "24") (name "LPCTRL3") (class "Default")
      (node (ref "R32") (pin "2") (pinfunction "2_2") (pintype "passive"))
      (node (ref "R35") (pin "2") (pinfunction "2_2") (pintype "passive"))
      (node (ref "R73") (pin "1") (pinfunction "1_1") (pintype "passive"))
    )
    (net (code "25") (name "LPCTRL4") (class "Default")
      (node (ref "R42") (pin "2") (pinfunction "2_2") (pintype "passive"))
      (node (ref "R45") (pin "2") (pinfunction "2_2") (pintype "passive"))
      (node (ref "R72") (pin "1") (pinfunction "1_1") (pintype "passive"))
    )
    (net (code "26") (name "LPCTRL5") (class "Default")
      (node (ref "R31") (pin "2") (pinfunction "2_2") (pintype "passive"))
      (node (ref "R34") (pin "2") (pinfunction "2_2") (pintype "passive"))
      (node (ref "R94") (pin "1") (pinfunction "1_1") (pintype "passive"))
    )
    (net (code "27") (name "LPCTRL6") (class "Default")
      (node (ref "R30") (pin "2") (pinfunction "2_2") (pintype "passive"))
      (node (ref "R33") (pin "2") (pinfunction "2_2") (pintype "passive"))
      (node (ref "R95") (pin "1") (pinfunction "1_1") (pintype "passive"))
    )
    (net (code "28") (name "NTC_IN1") (class "Default")
      (node (ref "R8") (pin "2") (pinfunction "2_2") (pintype "passive"))
      (node (ref "U3") (pin "99") (pinfunction "P2(4)_99") (pintype "bidirectional"))
    )
    (net (code "29") (name "Net-(C18-Pad1)") (class "Default")
      (node (ref "C18") (pin "1") (pinfunction "1_1") (pintype "passive"))
      (node (ref "J8") (pin "A") (pinfunction "G1_A") (pintype "bidirectional"))
      (node (ref "J8") (pin "B") (pinfunction "G1_B") (pintype "bidirectional"))
      (node (ref "J8") (pin "G1") (pinfunction "G1_G1") (pintype "bidirectional"))
      (node (ref "J8") (pin "S2") (pinfunction "G1_S2") (pintype "bidirectional"))
      (node (ref "J8") (pin "S3") (pinfunction "G1_S3") (pintype "bidirectional"))
      (node (ref "J8") (pin "S4") (pinfunction "G1_S4") (pintype "bidirectional"))
      (node (ref "R21") (pin "2") (pinfunction "2_2") (pintype "passive"))
    )
    (net (code "30") (name "Net-(C23-Pad1)") (class "Default")
      (node (ref "C23") (pin "1") (pinfunction "1_1") (pintype "passive"))
      (node (ref "R24") (pin "1") (pinfunction "1_1") (pintype "passive"))
      (node (ref "R27") (pin "2") (pinfunction "2_2") (pintype "passive"))
    )
    (net (code "31") (name "Net-(C24-Pad1)") (class "Default")
      (node (ref "C24") (pin "1") (pinfunction "1_1") (pintype "passive"))
      (node (ref "R25") (pin "1") (pinfunction "1_1") (pintype "passive"))
      (node (ref "R28") (pin "2") (pinfunction "2_2") (pintype "passive"))
    )
    (net (code "32") (name "Net-(C25-Pad1)") (class "Default")
      (node (ref "C25") (pin "1") (pinfunction "1_1") (pintype "passive"))
      (node (ref "R26") (pin "1") (pinfunction "1_1") (pintype "passive"))
      (node (ref "R29") (pin "2") (pinfunction "2_2") (pintype "passive"))
    )
    (net (code "33") (name "Net-(C31-Pad1)") (class "Default")
      (node (ref "C31") (pin "1") (pinfunction "1_1") (pintype "passive"))
      (node (ref "R36") (pin "1") (pinfunction "1_1") (pintype "passive"))
      (node (ref "R39") (pin "2") (pinfunction "2_2") (pintype "passive"))
    )
    (net (code "34") (name "Net-(C32-Pad1)") (class "Default")
      (node (ref "C32") (pin "1") (pinfunction "1_1") (pintype "passive"))
      (node (ref "R37") (pin "1") (pinfunction "1_1") (pintype "passive"))
      (node (ref "R40") (pin "2") (pinfunction "2_2") (pintype "passive"))
    )
    (net (code "35") (name "Net-(C33-Pad1)") (class "Default")
      (node (ref "C33") (pin "1") (pinfunction "1_1") (pintype "passive"))
      (node (ref "R38") (pin "1") (pinfunction "1_1") (pintype "passive"))
      (node (ref "R41") (pin "2") (pinfunction "2_2") (pintype "passive"))
    )
    (net (code "36") (name "Net-(IC1A-+IN)") (class "Default")
      (node (ref "C19") (pin "2") (pinfunction "2_2") (pintype "passive"))
      (node (ref "IC1") (pin "3") (pinfunction "+IN_3") (pintype "input"))
      (node (ref "R27") (pin "1") (pinfunction "1_1") (pintype "passive"))
    )
    (net (code "37") (name "Net-(IC1A--IN)") (class "Default")
      (node (ref "C23") (pin "2") (pinfunction "2_2") (pintype "passive"))
      (node (ref "IC1") (pin "1") (pinfunction "OUT_1") (pintype "output"))
      (node (ref "IC1") (pin "2") (pinfunction "-IN_2") (pintype "input"))
      (node (ref "R30") (pin "1") (pinfunction "1_1") (pintype "passive"))
    )
    (net (code "38") (name "Net-(IC1B-+IN)") (class "Default")
      (node (ref "C20") (pin "2") (pinfunction "2_2") (pintype "passive"))
      (node (ref "IC1") (pin "5") (pinfunction "+IN_5") (pintype "input"))
      (node (ref "R28") (pin "1") (pinfunction "1_1") (pintype "passive"))
    )
    (net (code "39") (name "Net-(IC1B--IN)") (class "Default")
      (node (ref "C24") (pin "2") (pinfunction "2_2") (pintype "passive"))
      (node (ref "IC1") (pin "6") (pinfunction "-IN_6") (pintype "input"))
      (node (ref "IC1") (pin "7") (pinfunction "OUT_7") (pintype "output"))
      (node (ref "R31") (pin "1") (pinfunction "1_1") (pintype "passive"))
    )
    (net (code "40") (name "Net-(IC1C--IN)") (class "Default")
      (node (ref "IC1") (pin "8") (pinfunction "OUT_8") (pintype "output"))
      (node (ref "IC1") (pin "9") (pinfunction "-IN_9") (pintype "input"))
    )
    (net (code "41") (name "Net-(IC1D-+IN)") (class "Default")
      (node (ref "C21") (pin "2") (pinfunction "2_2") (pintype "passive"))
      (node (ref "IC1") (pin "12") (pinfunction "+IN_12") (pintype "input"))
      (node (ref "R29") (pin "1") (pinfunction "1_1") (pintype "passive"))
    )
    (net (code "42") (name "Net-(IC1D--IN)") (class "Default")
      (node (ref "C25") (pin "2") (pinfunction "2_2") (pintype "passive"))
      (node (ref "IC1") (pin "13") (pinfunction "-IN_13") (pintype "input"))
      (node (ref "IC1") (pin "14") (pinfunction "OUT_14") (pintype "output"))
      (node (ref "R32") (pin "1") (pinfunction "1_1") (pintype "passive"))
    )
    (net (code "43") (name "Net-(IC2A--IN)") (class "Default")
      (node (ref "IC2") (pin "1") (pinfunction "OUT_1") (pintype "output"))
      (node (ref "IC2") (pin "2") (pinfunction "-IN_2") (pintype "input"))
    )
    (net (code "44") (name "Net-(IC2B-+IN)") (class "Default")
      (node (ref "C27") (pin "2") (pinfunction "2_2") (pintype "passive"))
      (node (ref "IC2") (pin "5") (pinfunction "+IN_5") (pintype "input"))
      (node (ref "R39") (pin "1") (pinfunction "1_1") (pintype "passive"))
    )
    (net (code "45") (name "Net-(IC2B--IN)") (class "Default")
      (node (ref "C31") (pin "2") (pinfunction "2_2") (pintype "passive"))
      (node (ref "IC2") (pin "6") (pinfunction "-IN_6") (pintype "input"))
      (node (ref "IC2") (pin "7") (pinfunction "OUT_7") (pintype "output"))
      (node (ref "R42") (pin "1") (pinfunction "1_1") (pintype "passive"))
    )
    (net (code "46") (name "Net-(IC2C-+IN)") (class "Default")
      (node (ref "C29") (pin "2") (pinfunction "2_2") (pintype "passive"))
      (node (ref "IC2") (pin "10") (pinfunction "+IN_10") (pintype "input"))
      (node (ref "R41") (pin "1") (pinfunction "1_1") (pintype "passive"))
    )
    (net (code "47") (name "Net-(IC2C--IN)") (class "Default")
      (node (ref "C33") (pin "2") (pinfunction "2_2") (pintype "passive"))
      (node (ref "IC2") (pin "8") (pinfunction "OUT_8") (pintype "output"))
      (node (ref "IC2") (pin "9") (pinfunction "-IN_9") (pintype "input"))
      (node (ref "R44") (pin "1") (pinfunction "1_1") (pintype "passive"))
    )
    (net (code "48") (name "Net-(IC2D-+IN)") (class "Default")
      (node (ref "C28") (pin "2") (pinfunction "2_2") (pintype "passive"))
      (node (ref "IC2") (pin "12") (pinfunction "+IN_12") (pintype "input"))
      (node (ref "R40") (pin "1") (pinfunction "1_1") (pintype "passive"))
    )
    (net (code "49") (name "Net-(IC2D--IN)") (class "Default")
      (node (ref "C32") (pin "2") (pinfunction "2_2") (pintype "passive"))
      (node (ref "IC2") (pin "13") (pinfunction "-IN_13") (pintype "input"))
      (node (ref "IC2") (pin "14") (pinfunction "OUT_14") (pintype "output"))
      (node (ref "R43") (pin "1") (pinfunction "1_1") (pintype "passive"))
    )
    (net (code "50") (name "Net-(J8-PadD+)") (class "Default")
      (node (ref "J8") (pin "D+") (pinfunction "D+_D+") (pintype "bidirectional"))
      (node (ref "R15") (pin "1") (pinfunction "1_1") (pintype "passive"))
      (node (ref "R18") (pin "1") (pinfunction "1_1") (pintype "passive"))
    )
    (net (code "51") (name "Net-(J8-PadD-)") (class "Default")
      (node (ref "J8") (pin "D-") (pinfunction "D-_D-") (pintype "bidirectional"))
      (node (ref "R14") (pin "2") (pinfunction "2_2") (pintype "passive"))
      (node (ref "R17") (pin "1") (pinfunction "1_1") (pintype "passive"))
    )
    (net (code "52") (name "Net-(J9-Pad2)") (class "Default")
      (node (ref "J9") (pin "2") (pinfunction "2_2") (pintype "bidirectional"))
      (node (ref "R48") (pin "2") (pinfunction "2_2") (pintype "passive"))
    )
    (net (code "53") (name "Net-(J10-Pad2)") (class "Default")
      (node (ref "J10") (pin "2") (pinfunction "2_2") (pintype "bidirectional"))
      (node (ref "R51") (pin "2") (pinfunction "2_2") (pintype "passive"))
    )
    (net (code "54") (name "Net-(L2-1)") (class "Default")
      (node (ref "D6") (pin "C") (pinfunction "C_C") (pintype "passive"))
      (node (ref "L2") (pin "P$1") (pinfunction "1_P$1") (pintype "passive"))
      (node (ref "L3") (pin "1") (pinfunction "1_1") (pintype "passive"))
      (node (ref "Q1") (pin "C") (pinfunction "D_C") (pintype "passive"))
    )
    (net (code "55") (name "Net-(L4-1)") (class "Default")
      (node (ref "D7") (pin "C") (pinfunction "C_C") (pintype "passive"))
      (node (ref "L4") (pin "P$1") (pinfunction "1_P$1") (pintype "passive"))
      (node (ref "L5") (pin "1") (pinfunction "1_1") (pintype "passive"))
      (node (ref "Q2") (pin "C") (pinfunction "D_C") (pintype "passive"))
    )
    (net (code "56") (name "Net-(L6-1)") (class "Default")
      (node (ref "D8") (pin "C") (pinfunction "C_C") (pintype "passive"))
      (node (ref "L6") (pin "P$1") (pinfunction "1_P$1") (pintype "passive"))
      (node (ref "L7") (pin "1") (pinfunction "1_1") (pintype "passive"))
      (node (ref "Q5") (pin "C") (pinfunction "D_C") (pintype "passive"))
    )
    (net (code "57") (name "Net-(L8-1)") (class "Default")
      (node (ref "D9") (pin "C") (pinfunction "C_C") (pintype "passive"))
      (node (ref "L8") (pin "P$1") (pinfunction "1_P$1") (pintype "passive"))
      (node (ref "L9") (pin "1") (pinfunction "1_1") (pintype "passive"))
      (node (ref "Q6") (pin "C") (pinfunction "D_C") (pintype "passive"))
    )
    (net (code "58") (name "Net-(L10-1)") (class "Default")
      (node (ref "D10") (pin "C") (pinfunction "C_C") (pintype "passive"))
      (node (ref "L10") (pin "P$1") (pinfunction "1_P$1") (pintype "passive"))
      (node (ref "L11") (pin "1") (pinfunction "1_1") (pintype "passive"))
      (node (ref "Q9") (pin "C") (pinfunction "D_C") (pintype "passive"))
    )
    (net (code "59") (name "Net-(L12-1)") (class "Default")
      (node (ref "D11") (pin "C") (pinfunction "C_C") (pintype "passive"))
      (node (ref "L12") (pin "P$1") (pinfunction "1_P$1") (pintype "passive"))
      (node (ref "L13") (pin "1") (pinfunction "1_1") (pintype "passive"))
      (node (ref "Q10") (pin "C") (pinfunction "D_C") (pintype "passive"))
    )
    (net (code "60") (name "Net-(LED1-PadA)") (class "Default")
      (node (ref "LED1") (pin "A") (pinfunction "A_A") (pintype "passive"))
      (node (ref "R11") (pin "1") (pinfunction "1_1") (pintype "passive"))
    )
    (net (code "61") (name "Net-(LED2-PadA)") (class "Default")
      (node (ref "LED2") (pin "A") (pinfunction "A_A") (pintype "passive"))
      (node (ref "R12") (pin "1") (pinfunction "1_1") (pintype "passive"))
    )
    (net (code "62") (name "Net-(LED3-PadA)") (class "Default")
      (node (ref "LED3") (pin "A") (pinfunction "A_A") (pintype "passive"))
      (node (ref "R13") (pin "1") (pinfunction "1_1") (pintype "passive"))
    )
    (net (code "63") (name "Net-(Q1-G)") (class "Default")
      (node (ref "Q1") (pin "B") (pinfunction "G_B") (pintype "passive"))
      (node (ref "R64") (pin "1") (pinfunction "1_1") (pintype "passive"))
      (node (ref "ZD1") (pin "A") (pinfunction "A_A") (pintype "passive"))
    )
    (net (code "64") (name "Net-(Q1-S)") (class "Default")
      (node (ref "Q1") (pin "E") (pinfunction "S_E") (pintype "passive"))
      (node (ref "R66") (pin "2") (pinfunction "2_2") (pintype "passive"))
      (node (ref "U4") (pin "7") (pinfunction "CSN_7") (pintype "bidirectional"))
    )
    (net (code "65") (name "Net-(Q2-G)") (class "Default")
      (node (ref "Q2") (pin "B") (pinfunction "G_B") (pintype "passive"))
      (node (ref "R65") (pin "1") (pinfunction "1_1") (pintype "passive"))
      (node (ref "ZD2") (pin "A") (pinfunction "A_A") (pintype "passive"))
    )
    (net (code "66") (name "Net-(Q2-S)") (class "Default")
      (node (ref "Q2") (pin "E") (pinfunction "S_E") (pintype "passive"))
      (node (ref "R67") (pin "2") (pinfunction "2_2") (pintype "passive"))
      (node (ref "U5") (pin "7") (pinfunction "CSN_7") (pintype "bidirectional"))
    )
    (net (code "67") (name "Net-(Q3-G)") (class "Default")
      (node (ref "Q3") (pin "4") (pinfunction "G_4") (pintype "passive"))
      (node (ref "R68") (pin "1") (pinfunction "1_1") (pintype "passive"))
      (node (ref "R70") (pin "2") (pinfunction "2_2") (pintype "passive"))
    )
    (net (code "68") (name "Net-(Q4-G)") (class "Default")
      (node (ref "Q4") (pin "4") (pinfunction "G_4") (pintype "passive"))
      (node (ref "R69") (pin "1") (pinfunction "1_1") (pintype "passive"))
      (node (ref "R71") (pin "2") (pinfunction "2_2") (pintype "passive"))
    )
    (net (code "69") (name "Net-(Q5-G)") (class "Default")
      (node (ref "Q5") (pin "B") (pinfunction "G_B") (pintype "passive"))
      (node (ref "R86") (pin "1") (pinfunction "1_1") (pintype "passive"))
      (node (ref "ZD3") (pin "A") (pinfunction "A_A") (pintype "passive"))
    )
    (net (code "70") (name "Net-(Q5-S)") (class "Default")
      (node (ref "Q5") (pin "E") (pinfunction "S_E") (pintype "passive"))
      (node (ref "R88") (pin "2") (pinfunction "2_2") (pintype "passive"))
      (node (ref "U6") (pin "7") (pinfunction "CSN_7") (pintype "bidirectional"))
    )
    (net (code "71") (name "Net-(Q6-G)") (class "Default")
      (node (ref "Q6") (pin "B") (pinfunction "G_B") (pintype "passive"))
      (node (ref "R87") (pin "1") (pinfunction "1_1") (pintype "passive"))
      (node (ref "ZD4") (pin "A") (pinfunction "A_A") (pintype "passive"))
    )
    (net (code "72") (name "Net-(Q6-S)") (class "Default")
      (node (ref "Q6") (pin "E") (pinfunction "S_E") (pintype "passive"))
      (node (ref "R89") (pin "2") (pinfunction "2_2") (pintype "passive"))
      (node (ref "U7") (pin "7") (pinfunction "CSN_7") (pintype "bidirectional"))
    )
    (net (code "73") (name "Net-(Q7-G)") (class "Default")
      (node (ref "Q7") (pin "4") (pinfunction "G_4") (pintype "passive"))
      (node (ref "R90") (pin "1") (pinfunction "1_1") (pintype "passive"))
      (node (ref "R92") (pin "2") (pinfunction "2_2") (pintype "passive"))
    )
    (net (code "74") (name "Net-(Q8-G)") (class "Default")
      (node (ref "Q8") (pin "4") (pinfunction "G_4") (pintype "passive"))
      (node (ref "R91") (pin "1") (pinfunction "1_1") (pintype "passive"))
      (node (ref "R93") (pin "2") (pinfunction "2_2") (pintype "passive"))
    )
    (net (code "75") (name "Net-(Q9-G)") (class "Default")
      (node (ref "Q9") (pin "B") (pinfunction "G_B") (pintype "passive"))
      (node (ref "R108") (pin "1") (pinfunction "1_1") (pintype "passive"))
      (node (ref "ZD5") (pin "A") (pinfunction "A_A") (pintype "passive"))
    )
    (net (code "76") (name "Net-(Q9-S)") (class "Default")
      (node (ref "Q9") (pin "E") (pinfunction "S_E") (pintype "passive"))
      (node (ref "R110") (pin "2") (pinfunction "2_2") (pintype "passive"))
      (node (ref "U8") (pin "7") (pinfunction "CSN_7") (pintype "bidirectional"))
    )
    (net (code "77") (name "Net-(Q10-G)") (class "Default")
      (node (ref "Q10") (pin "B") (pinfunction "G_B") (pintype "passive"))
      (node (ref "R109") (pin "1") (pinfunction "1_1") (pintype "passive"))
      (node (ref "ZD6") (pin "A") (pinfunction "A_A") (pintype "passive"))
    )
    (net (code "78") (name "Net-(Q10-S)") (class "Default")
      (node (ref "Q10") (pin "E") (pinfunction "S_E") (pintype "passive"))
      (node (ref "R111") (pin "2") (pinfunction "2_2") (pintype "passive"))
      (node (ref "U9") (pin "7") (pinfunction "CSN_7") (pintype "bidirectional"))
    )
    (net (code "79") (name "Net-(Q11-G)") (class "Default")
      (node (ref "Q11") (pin "4") (pinfunction "G_4") (pintype "passive"))
      (node (ref "R112") (pin "1") (pinfunction "1_1") (pintype "passive"))
      (node (ref "R114") (pin "2") (pinfunction "2_2") (pintype "passive"))
    )
    (net (code "80") (name "Net-(Q12-G)") (class "Default")
      (node (ref "Q12") (pin "4") (pinfunction "G_4") (pintype "passive"))
      (node (ref "R113") (pin "1") (pinfunction "1_1") (pintype "passive"))
      (node (ref "R115") (pin "2") (pinfunction "2_2") (pintype "passive"))
    )
    (net (code "81") (name "Net-(U1-CB)") (class "Default")
      (node (ref "C2") (pin "1") (pinfunction "1_1") (pintype "passive"))
      (node (ref "U1") (pin "1") (pinfunction "CB_1") (pintype "bidirectional"))
    )
    (net (code "82") (name "Net-(U1-FB)") (class "Default")
      (node (ref "R1") (pin "1") (pinfunction "1_1") (pintype "passive"))
      (node (ref "R2") (pin "2") (pinfunction "2_2") (pintype "passive"))
      (node (ref "U1") (pin "3") (pinfunction "FB_3") (pintype "bidirectional"))
    )
    (net (code "83") (name "Net-(U1-SW)") (class "Default")
      (node (ref "C2") (pin "2") (pinfunction "2_2") (pintype "passive"))
      (node (ref "D3") (pin "C") (pinfunction "C_C") (pintype "passive"))
      (node (ref "L1") (pin "1") (pinfunction "1_1") (pintype "passive"))
      (node (ref "U1") (pin "6") (pinfunction "SW_6") (pintype "bidirectional"))
    )
    (net (code "84") (name "Net-(U1-{slash}SD)") (class "Default")
      (node (ref "D2") (pin "C") (pinfunction "C_C") (pintype "passive"))
      (node (ref "R3") (pin "2") (pinfunction "2_2") (pintype "passive"))
      (node (ref "U1") (pin "4") (pinfunction "/SD_4") (pintype "bidirectional"))
    )
    (net (code "85") (name "Net-(U3-P0(4))") (class "Default")
      (node (ref "C11") (pin "2") (pinfunction "2_2") (pintype "passive"))
      (node (ref "U3") (pin "76") (pinfunction "P0(4)_76") (pintype "bidirectional"))
    )
    (net (code "86") (name "Net-(U3-P5(4))") (class "Default")
      (node (ref "S1") (pin "8") (pinfunction "8_8") (pintype "passive"))
      (node (ref "U3") (pin "31") (pinfunction "P5(4)_31") (pintype "bidirectional"))
    )
    (net (code "87") (name "Net-(U3-P5(5))") (class "Default")
      (node (ref "S1") (pin "7") (pinfunction "7_7") (pintype "passive"))
      (node (ref "U3") (pin "32") (pinfunction "P5(5)_32") (pintype "bidirectional"))
    )
    (net (code "88") (name "Net-(U3-P5(6))") (class "Default")
      (node (ref "S1") (pin "6") (pinfunction "6_6") (pintype "passive"))
      (node (ref "U3") (pin "33") (pinfunction "P5(6)_33") (pintype "bidirectional"))
    )
    (net (code "89") (name "Net-(U3-P15(1)-XTALI)") (class "Default")
      (node (ref "S1") (pin "5") (pinfunction "5_5") (pintype "passive"))
      (node (ref "U3") (pin "43") (pinfunction "P15(1)-XTALI_43") (pintype "bidirectional"))
    )
    (net (code "90") (name "Net-(U3-VCCA)") (class "Default")
      (node (ref "C15") (pin "2") (pinfunction "2_2") (pintype "passive"))
      (node (ref "U3") (pin "63") (pinfunction "VCCA_63") (pintype "bidirectional"))
    )
    (net (code "91") (name "Net-(U4-COFF)") (class "Default")
      (node (ref "C43") (pin "2") (pinfunction "2_2") (pintype "passive"))
      (node (ref "R60") (pin "1") (pinfunction "1_1") (pintype "passive"))
      (node (ref "R61") (pin "2") (pinfunction "2_2") (pintype "passive"))
      (node (ref "U4") (pin "4") (pinfunction "COFF_4") (pintype "bidirectional"))
    )
    (net (code "92") (name "Net-(U4-IADJ)") (class "Default")
      (node (ref "C39") (pin "2") (pinfunction "2_2") (pintype "passive"))
      (node (ref "R49") (pin "2") (pinfunction "2_2") (pintype "passive"))
      (node (ref "R52") (pin "2") (pinfunction "2_2") (pintype "passive"))
      (node (ref "U4") (pin "2") (pinfunction "IADJ_2") (pintype "bidirectional"))
    )
    (net (code "93") (name "Net-(U4-PGATE)") (class "Default")
      (node (ref "R64") (pin "2") (pinfunction "2_2") (pintype "passive"))
      (node (ref "U4") (pin "6") (pinfunction "PGATE_6") (pintype "bidirectional"))
      (node (ref "ZD1") (pin "C") (pinfunction "C_C") (pintype "passive"))
    )
    (net (code "94") (name "Net-(U4-UVLO)") (class "Default")
      (node (ref "R56") (pin "2") (pinfunction "2_2") (pintype "passive"))
      (node (ref "R58") (pin "1") (pinfunction "1_1") (pintype "passive"))
      (node (ref "U4") (pin "1") (pinfunction "UVLO_1") (pintype "bidirectional"))
    )
    (net (code "95") (name "Net-(U4-VCC)") (class "Default")
      (node (ref "C45") (pin "1") (pinfunction "1_1") (pintype "passive"))
      (node (ref "U4") (pin "9") (pinfunction "VCC_9") (pintype "bidirectional"))
    )
    (net (code "96") (name "Net-(U5-COFF)") (class "Default")
      (node (ref "C44") (pin "2") (pinfunction "2_2") (pintype "passive"))
      (node (ref "R62") (pin "1") (pinfunction "1_1") (pintype "passive"))
      (node (ref "R63") (pin "2") (pinfunction "2_2") (pintype "passive"))
      (node (ref "U5") (pin "4") (pinfunction "COFF_4") (pintype "bidirectional"))
    )
    (net (code "97") (name "Net-(U5-IADJ)") (class "Default")
      (node (ref "C40") (pin "2") (pinfunction "2_2") (pintype "passive"))
      (node (ref "R50") (pin "2") (pinfunction "2_2") (pintype "passive"))
      (node (ref "R53") (pin "2") (pinfunction "2_2") (pintype "passive"))
      (node (ref "U5") (pin "2") (pinfunction "IADJ_2") (pintype "bidirectional"))
    )
    (net (code "98") (name "Net-(U5-PGATE)") (class "Default")
      (node (ref "R65") (pin "2") (pinfunction "2_2") (pintype "passive"))
      (node (ref "U5") (pin "6") (pinfunction "PGATE_6") (pintype "bidirectional"))
      (node (ref "ZD2") (pin "C") (pinfunction "C_C") (pintype "passive"))
    )
    (net (code "99") (name "Net-(U5-UVLO)") (class "Default")
      (node (ref "R57") (pin "2") (pinfunction "2_2") (pintype "passive"))
      (node (ref "R59") (pin "1") (pinfunction "1_1") (pintype "passive"))
      (node (ref "U5") (pin "1") (pinfunction "UVLO_1") (pintype "bidirectional"))
    )
    (net (code "100") (name "Net-(U5-VCC)") (class "Default")
      (node (ref "C46") (pin "1") (pinfunction "1_1") (pintype "passive"))
      (node (ref "U5") (pin "9") (pinfunction "VCC_9") (pintype "bidirectional"))
    )
    (net (code "101") (name "Net-(U6-COFF)") (class "Default")
      (node (ref "C59") (pin "2") (pinfunction "2_2") (pintype "passive"))
      (node (ref "R82") (pin "1") (pinfunction "1_1") (pintype "passive"))
      (node (ref "R83") (pin "2") (pinfunction "2_2") (pintype "passive"))
      (node (ref "U6") (pin "4") (pinfunction "COFF_4") (pintype "bidirectional"))
    )
    (net (code "102") (name "Net-(U6-IADJ)") (class "Default")
      (node (ref "C55") (pin "2") (pinfunction "2_2") (pintype "passive"))
      (node (ref "R72") (pin "2") (pinfunction "2_2") (pintype "passive"))
      (node (ref "R74") (pin "2") (pinfunction "2_2") (pintype "passive"))
      (node (ref "U6") (pin "2") (pinfunction "IADJ_2") (pintype "bidirectional"))
    )
    (net (code "103") (name "Net-(U6-PGATE)") (class "Default")
      (node (ref "R86") (pin "2") (pinfunction "2_2") (pintype "passive"))
      (node (ref "U6") (pin "6") (pinfunction "PGATE_6") (pintype "bidirectional"))
      (node (ref "ZD3") (pin "C") (pinfunction "C_C") (pintype "passive"))
    )
    (net (code "104") (name "Net-(U6-UVLO)") (class "Default")
      (node (ref "R78") (pin "2") (pinfunction "2_2") (pintype "passive"))
      (node (ref "R80") (pin "1") (pinfunction "1_1") (pintype "passive"))
      (node (ref "U6") (pin "1") (pinfunction "UVLO_1") (pintype "bidirectional"))
    )
    (net (code "105") (name "Net-(U6-VCC)") (class "Default")
      (node (ref "C61") (pin "1") (pinfunction "1_1") (pintype "passive"))
      (node (ref "U6") (pin "9") (pinfunction "VCC_9") (pintype "bidirectional"))
    )
    (net (code "106") (name "Net-(U7-COFF)") (class "Default")
      (node (ref "C60") (pin "2") (pinfunction "2_2") (pintype "passive"))
      (node (ref "R84") (pin "1") (pinfunction "1_1") (pintype "passive"))
      (node (ref "R85") (pin "2") (pinfunction "2_2") (pintype "passive"))
      (node (ref "U7") (pin "4") (pinfunction "COFF_4") (pintype "bidirectional"))
    )
    (net (code "107") (name "Net-(U7-IADJ)") (class "Default")
      (node (ref "C56") (pin "2") (pinfunction "2_2") (pintype "passive"))
      (node (ref "R73") (pin "2") (pinfunction "2_2") (pintype "passive"))
      (node (ref "R75") (pin "2") (pinfunction "2_2") (pintype "passive"))
      (node (ref "U7") (pin "2") (pinfunction "IADJ_2") (pintype "bidirectional"))
    )
    (net (code "108") (name "Net-(U7-PGATE)") (class "Default")
      (node (ref "R87") (pin "2") (pinfunction "2_2") (pintype "passive"))
      (node (ref "U7") (pin "6") (pinfunction "PGATE_6") (pintype "bidirectional"))
      (node (ref "ZD4") (pin "C") (pinfunction "C_C") (pintype "passive"))
    )
    (net (code "109") (name "Net-(U7-UVLO)") (class "Default")
      (node (ref "R79") (pin "2") (pinfunction "2_2") (pintype "passive"))
      (node (ref "R81") (pin "1") (pinfunction "1_1") (pintype "passive"))
      (node (ref "U7") (pin "1") (pinfunction "UVLO_1") (pintype "bidirectional"))
    )
    (net (code "110") (name "Net-(U7-VCC)") (class "Default")
      (node (ref "C62") (pin "1") (pinfunction "1_1") (pintype "passive"))
      (node (ref "U7") (pin "9") (pinfunction "VCC_9") (pintype "bidirectional"))
    )
    (net (code "111") (name "Net-(U8-COFF)") (class "Default")
      (node (ref "C75") (pin "2") (pinfunction "2_2") (pintype "passive"))
      (node (ref "R104") (pin "1") (pinfunction "1_1") (pintype "passive"))
      (node (ref "R105") (pin "2") (pinfunction "2_2") (pintype "passive"))
      (node (ref "U8") (pin "4") (pinfunction "COFF_4") (pintype "bidirectional"))
    )
    (net (code "112") (name "Net-(U8-IADJ)") (class "Default")
      (node (ref "C71") (pin "2") (pinfunction "2_2") (pintype "passive"))
      (node (ref "R94") (pin "2") (pinfunction "2_2") (pintype "passive"))
      (node (ref "R96") (pin "2") (pinfunction "2_2") (pintype "passive"))
      (node (ref "U8") (pin "2") (pinfunction "IADJ_2") (pintype "bidirectional"))
    )
    (net (code "113") (name "Net-(U8-PGATE)") (class "Default")
      (node (ref "R108") (pin "2") (pinfunction "2_2") (pintype "passive"))
      (node (ref "U8") (pin "6") (pinfunction "PGATE_6") (pintype "bidirectional"))
      (node (ref "ZD5") (pin "C") (pinfunction "C_C") (pintype "passive"))
    )
    (net (code "114") (name "Net-(U8-UVLO)") (class "Default")
      (node (ref "R100") (pin "2") (pinfunction "2_2") (pintype "passive"))
      (node (ref "R102") (pin "1") (pinfunction "1_1") (pintype "passive"))
      (node (ref "U8") (pin "1") (pinfunction "UVLO_1") (pintype "bidirectional"))
    )
    (net (code "115") (name "Net-(U8-VCC)") (class "Default")
      (node (ref "C77") (pin "1") (pinfunction "1_1") (pintype "passive"))
      (node (ref "U8") (pin "9") (pinfunction "VCC_9") (pintype "bidirectional"))
    )
    (net (code "116") (name "Net-(U9-COFF)") (class "Default")
      (node (ref "C76") (pin "2") (pinfunction "2_2") (pintype "passive"))
      (node (ref "R106") (pin "1") (pinfunction "1_1") (pintype "passive"))
      (node (ref "R107") (pin "2") (pinfunction "2_2") (pintype "passive"))
      (node (ref "U9") (pin "4") (pinfunction "COFF_4") (pintype "bidirectional"))
    )
    (net (code "117") (name "Net-(U9-IADJ)") (class "Default")
      (node (ref "C72") (pin "2") (pinfunction "2_2") (pintype "passive"))
      (node (ref "R95") (pin "2") (pinfunction "2_2") (pintype "passive"))
      (node (ref "R97") (pin "2") (pinfunction "2_2") (pintype "passive"))
      (node (ref "U9") (pin "2") (pinfunction "IADJ_2") (pintype "bidirectional"))
    )
    (net (code "118") (name "Net-(U9-PGATE)") (class "Default")
      (node (ref "R109") (pin "2") (pinfunction "2_2") (pintype "passive"))
      (node (ref "U9") (pin "6") (pinfunction "PGATE_6") (pintype "bidirectional"))
      (node (ref "ZD6") (pin "C") (pinfunction "C_C") (pintype "passive"))
    )
    (net (code "119") (name "Net-(U9-UVLO)") (class "Default")
      (node (ref "R101") (pin "2") (pinfunction "2_2") (pintype "passive"))
      (node (ref "R103") (pin "1") (pinfunction "1_1") (pintype "passive"))
      (node (ref "U9") (pin "1") (pinfunction "UVLO_1") (pintype "bidirectional"))
    )
    (net (code "120") (name "Net-(U9-VCC)") (class "Default")
      (node (ref "C78") (pin "1") (pinfunction "1_1") (pintype "passive"))
      (node (ref "U9") (pin "9") (pinfunction "VCC_9") (pintype "bidirectional"))
    )
    (net (code "121") (name "OFF1") (class "Default")
      (node (ref "R55") (pin "2") (pinfunction "2_2") (pintype "passive"))
      (node (ref "U3") (pin "17") (pinfunction "P5(1)_17") (pintype "bidirectional"))
      (node (ref "U5") (pin "3") (pinfunction "EN_3") (pintype "bidirectional"))
    )
    (net (code "122") (name "OFF2") (class "Default")
      (node (ref "R54") (pin "2") (pinfunction "2_2") (pintype "passive"))
      (node (ref "U3") (pin "1") (pinfunction "P2(5)_1") (pintype "bidirectional"))
      (node (ref "U4") (pin "3") (pinfunction "EN_3") (pintype "bidirectional"))
    )
    (net (code "123") (name "OFF3") (class "Default")
      (node (ref "R77") (pin "2") (pinfunction "2_2") (pintype "passive"))
      (node (ref "U3") (pin "84") (pinfunction "P4(6)_84") (pintype "bidirectional"))
      (node (ref "U7") (pin "3") (pinfunction "EN_3") (pintype "bidirectional"))
    )
    (net (code "124") (name "OFF4") (class "Default")
      (node (ref "R76") (pin "2") (pinfunction "2_2") (pintype "passive"))
      (node (ref "U3") (pin "92") (pinfunction "P6(3)_92") (pintype "bidirectional"))
      (node (ref "U6") (pin "3") (pinfunction "EN_3") (pintype "bidirectional"))
    )
    (net (code "125") (name "OFF5") (class "Default")
      (node (ref "R98") (pin "2") (pinfunction "2_2") (pintype "passive"))
      (node (ref "U3") (pin "80") (pinfunction "P4(2)_80") (pintype "bidirectional"))
      (node (ref "U8") (pin "3") (pinfunction "EN_3") (pintype "bidirectional"))
    )
    (net (code "126") (name "OFF6") (class "Default")
      (node (ref "R99") (pin "2") (pinfunction "2_2") (pintype "passive"))
      (node (ref "U3") (pin "82") (pinfunction "P4(4)_82") (pintype "bidirectional"))
      (node (ref "U9") (pin "3") (pinfunction "EN_3") (pintype "bidirectional"))
    )
    (net (code "127") (name "PINCH_1") (class "Default")
      (node (ref "R69") (pin "2") (pinfunction "2_2") (pintype "passive"))
      (node (ref "U3") (pin "9") (pinfunction "P6(7)_9") (pintype "bidirectional"))
    )
    (net (code "128") (name "PINCH_2") (class "Default")
      (node (ref "R68") (pin "2") (pinfunction "2_2") (pintype "passive"))
      (node (ref "U3") (pin "2") (pinfunction "P2(6)_2") (pintype "bidirectional"))
    )
    (net (code "129") (name "PINCH_3") (class "Default")
      (node (ref "R91") (pin "2") (pinfunction "2_2") (pintype "passive"))
      (node (ref "U3") (pin "85") (pinfunction "P4(7)_85") (pintype "bidirectional"))
    )
    (net (code "130") (name "PINCH_4") (class "Default")
      (node (ref "R90") (pin "2") (pinfunction "2_2") (pintype "passive"))
      (node (ref "U3") (pin "93") (pinfunction "P15(4)_93") (pintype "bidirectional"))
    )
    (net (code "131") (name "PINCH_5") (class "Default")
      (node (ref "R112") (pin "2") (pinfunction "2_2") (pintype "passive"))
      (node (ref "U3") (pin "81") (pinfunction "P4(3)_81") (pintype "bidirectional"))
    )
    (net (code "132") (name "PINCH_6") (class "Default")
      (node (ref "R113") (pin "2") (pinfunction "2_2") (pintype "passive"))
      (node (ref "U3") (pin "83") (pinfunction "P4(5)_83") (pintype "bidirectional"))
    )
    (net (code "133") (name "RECEIVE") (class "Default")
      (node (ref "U2") (pin "1") (pinfunction "R_1") (pintype "bidirectional"))
      (node (ref "U3") (pin "56") (pinfunction "KHZXTALI-P15(3)_56") (pintype "bidirectional"))
    )
    (net (code "134") (name "SCL") (class "Default")
      (node (ref "J5") (pin "1") (pinfunction "1_1") (pintype "bidirectional"))
      (node (ref "R6") (pin "1") (pinfunction "1_1") (pintype "passive"))
      (node (ref "U3") (pin "4") (pinfunction "P12(4)-SCL0-SIO0_4") (pintype "bidirectional"))
    )
    (net (code "135") (name "SDA") (class "Default")
      (node (ref "J5") (pin "2") (pinfunction "2_2") (pintype "bidirectional"))
      (node (ref "R7") (pin "2") (pinfunction "2_2") (pintype "passive"))
      (node (ref "U3") (pin "5") (pinfunction "P12(5)-SDA0-SIO0_5") (pintype "bidirectional"))
    )
    (net (code "136") (name "SENSE1") (class "Default")
      (node (ref "R48") (pin "1") (pinfunction "1_1") (pintype "passive"))
      (node (ref "U3") (pin "8") (pinfunction "P6(6)_8") (pintype "bidirectional"))
    )
    (net (code "137") (name "SENSE2") (class "Default")
      (node (ref "R51") (pin "1") (pinfunction "1_1") (pintype "passive"))
      (node (ref "U3") (pin "7") (pinfunction "P6(5)_7") (pintype "bidirectional"))
    )
    (net (code "138") (name "SWDCLK") (class "Default")
      (node (ref "J6") (pin "4") (pinfunction "4_4") (pintype "bidirectional"))
      (node (ref "P1") (pin "4") (pinfunction "4_4") (pintype "bidirectional"))
      (node (ref "U3") (pin "21") (pinfunction "P1(1)-TCK-SWDCK_21") (pintype "bidirectional"))
    )
    (net (code "139") (name "SWDIO") (class "Default")
      (node (ref "J6") (pin "5") (pinfunction "5_5") (pintype "bidirectional"))
      (node (ref "P1") (pin "2") (pinfunction "2_2") (pintype "bidirectional"))
      (node (ref "U3") (pin "20") (pinfunction "P1(0)-TMS-SWDIO_20") (pintype "bidirectional"))
    )
    (net (code "140") (name "TEMP") (class "Default")
      (node (ref "R19") (pin "2") (pinfunction "2_2") (pintype "passive"))
      (node (ref "R20") (pin "1") (pinfunction "1_1") (pintype "passive"))
      (node (ref "U3") (pin "3") (pinfunction "P2(7)_3") (pintype "bidirectional"))
    )
    (net (code "141") (name "TRANSMIT") (class "Default")
      (node (ref "U2") (pin "4") (pinfunction "D_4") (pintype "bidirectional"))
      (node (ref "U3") (pin "51") (pinfunction "P3(6)_51") (pintype "bidirectional"))
    )
    (net (code "142") (name "USBD+") (class "Default")
      (node (ref "R15") (pin "2") (pinfunction "2_2") (pintype "passive"))
      (node (ref "U3") (pin "35") (pinfunction "P15(6)-USBD+_35") (pintype "bidirectional"))
    )
    (net (code "143") (name "USBD-") (class "Default")
      (node (ref "R14") (pin "1") (pinfunction "1_1") (pintype "passive"))
      (node (ref "U3") (pin "36") (pinfunction "P15(7)-USBD-_36") (pintype "bidirectional"))
    )
    (net (code "144") (name "VBUS") (class "Default")
      (node (ref "D5") (pin "A") (pinfunction "A_A") (pintype "passive"))
      (node (ref "J8") (pin "VBUS") (pinfunction "VBUS_VBUS") (pintype "bidirectional"))
      (node (ref "R16") (pin "1") (pinfunction "1_1") (pintype "passive"))
    )
    (net (code "145") (name "VCCD") (class "Default")
      (node (ref "C10") (pin "2") (pinfunction "2_2") (pintype "passive"))
      (node (ref "U3") (pin "39") (pinfunction "VCCD_39") (pintype "bidirectional"))
      (node (ref "U3") (pin "86") (pinfunction "VCCD_86") (pintype "bidirectional"))
    )
    (net (code "146") (name "VINREG") (class "Default")
      (node (ref "C1") (pin "1") (pinfunction "1_1") (pintype "passive"))
      (node (ref "D1") (pin "C") (pinfunction "C_C") (pintype "passive"))
      (node (ref "R3") (pin "1") (pinfunction "1_1") (pintype "passive"))
      (node (ref "U1") (pin "5") (pinfunction "VIN_5") (pintype "bidirectional"))
    )
    (net (code "147") (name "VRAIL") (class "Default")
      (node (ref "C35") (pin "1") (pinfunction "1_1") (pintype "passive"))
      (node (ref "C36") (pin "1") (pinfunction "1_1") (pintype "passive"))
      (node (ref "C37") (pin "1") (pinfunction "1_1") (pintype "passive"))
      (node (ref "C38") (pin "1") (pinfunction "1_1") (pintype "passive"))
      (node (ref "C41") (pin "1") (pinfunction "1_1") (pintype "passive"))
      (node (ref "C42") (pin "1") (pinfunction "1_1") (pintype "passive"))
      (node (ref "C45") (pin "2") (pinfunction "2_2") (pintype "passive"))
      (node (ref "C46") (pin "2") (pinfunction "2_2") (pintype "passive"))
      (node (ref "C51") (pin "1") (pinfunction "1_1") (pintype "passive"))
      (node (ref "C52") (pin "1") (pinfunction "1_1") (pintype "passive"))
      (node (ref "C53") (pin "1") (pinfunction "1_1") (pintype "passive"))
      (node (ref "C54") (pin "1") (pinfunction "1_1") (pintype "passive"))
      (node (ref "C57") (pin "1") (pinfunction "1_1") (pintype "passive"))
      (node (ref "C58") (pin "1") (pinfunction "1_1") (pintype "passive"))
      (node (ref "C61") (pin "2") (pinfunction "2_2") (pintype "passive"))
      (node (ref "C62") (pin "2") (pinfunction "2_2") (pintype "passive"))
      (node (ref "C67") (pin "1") (pinfunction "1_1") (pintype "passive"))
      (node (ref "C68") (pin "1") (pinfunction "1_1") (pintype "passive"))
      (node (ref "C69") (pin "1") (pinfunction "1_1") (pintype "passive"))
      (node (ref "C70") (pin "1") (pinfunction "1_1") (pintype "passive"))
      (node (ref "C73") (pin "1") (pinfunction "1_1") (pintype "passive"))
      (node (ref "C74") (pin "1") (pinfunction "1_1") (pintype "passive"))
      (node (ref "C77") (pin "2") (pinfunction "2_2") (pintype "passive"))
      (node (ref "C78") (pin "2") (pinfunction "2_2") (pintype "passive"))
      (node (ref "D1") (pin "A") (pinfunction "A_A") (pintype "passive"))
      (node (ref "J1") (pin "1") (pinfunction "1_1") (pintype "bidirectional"))
      (node (ref "R102") (pin "2") (pinfunction "2_2") (pintype "passive"))
      (node (ref "R103") (pin "2") (pinfunction "2_2") (pintype "passive"))
      (node (ref "R104") (pin "2") (pinfunction "2_2") (pintype "passive"))
      (node (ref "R106") (pin "2") (pinfunction "2_2") (pintype "passive"))
      (node (ref "R110") (pin "1") (pinfunction "1_1") (pintype "passive"))
      (node (ref "R111") (pin "1") (pinfunction "1_1") (pintype "passive"))
      (node (ref "R22") (pin "2") (pinfunction "2_2") (pintype "passive"))
      (node (ref "R58") (pin "2") (pinfunction "2_2") (pintype "passive"))
      (node (ref "R59") (pin "2") (pinfunction "2_2") (pintype "passive"))
      (node (ref "R60") (pin "2") (pinfunction "2_2") (pintype "passive"))
      (node (ref "R62") (pin "2") (pinfunction "2_2") (pintype "passive"))
      (node (ref "R66") (pin "1") (pinfunction "1_1") (pintype "passive"))
      (node (ref "R67") (pin "1") (pinfunction "1_1") (pintype "passive"))
      (node (ref "R80") (pin "2") (pinfunction "2_2") (pintype "passive"))
      (node (ref "R81") (pin "2") (pinfunction "2_2") (pintype "passive"))
      (node (ref "R82") (pin "2") (pinfunction "2_2") (pintype "passive"))
      (node (ref "R84") (pin "2") (pinfunction "2_2") (pintype "passive"))
      (node (ref "R88") (pin "1") (pinfunction "1_1") (pintype "passive"))
      (node (ref "R89") (pin "1") (pinfunction "1_1") (pintype "passive"))
      (node (ref "U4") (pin "10") (pinfunction "VIN_10") (pintype "bidirectional"))
      (node (ref "U4") (pin "8") (pinfunction "CSP_8") (pintype "bidirectional"))
      (node (ref "U5") (pin "10") (pinfunction "VIN_10") (pintype "bidirectional"))
      (node (ref "U5") (pin "8") (pinfunction "CSP_8") (pintype "bidirectional"))
      (node (ref "U6") (pin "10") (pinfunction "VIN_10") (pintype "bidirectional"))
      (node (ref "U6") (pin "8") (pinfunction "CSP_8") (pintype "bidirectional"))
      (node (ref "U7") (pin "10") (pinfunction "VIN_10") (pintype "bidirectional"))
      (node (ref "U7") (pin "8") (pinfunction "CSP_8") (pintype "bidirectional"))
      (node (ref "U8") (pin "10") (pinfunction "VIN_10") (pintype "bidirectional"))
      (node (ref "U8") (pin "8") (pinfunction "CSP_8") (pintype "bidirectional"))
      (node (ref "U9") (pin "10") (pinfunction "VIN_10") (pintype "bidirectional"))
      (node (ref "U9") (pin "8") (pinfunction "CSP_8") (pintype "bidirectional"))
    )
    (net (code "148") (name "VSENSE") (class "Default")
      (node (ref "R22") (pin "1") (pinfunction "1_1") (pintype "passive"))
      (node (ref "R23") (pin "2") (pinfunction "2_2") (pintype "passive"))
      (node (ref "U3") (pin "71") (pinfunction "P0(0)_71") (pintype "bidirectional"))
    )
    (net (code "149") (name "unconnected-(FID1-PadP$1)") (class "Default")
      (node (ref "FID1") (pin "P$1") (pinfunction "P$1_P$1") (pintype "bidirectional"))
    )
    (net (code "150") (name "unconnected-(FID2-PadP$1)") (class "Default")
      (node (ref "FID2") (pin "P$1") (pinfunction "P$1_P$1") (pintype "bidirectional"))
    )
    (net (code "151") (name "unconnected-(FID3-PadP$1)") (class "Default")
      (node (ref "FID3") (pin "P$1") (pinfunction "P$1_P$1") (pintype "bidirectional"))
    )
    (net (code "152") (name "unconnected-(IC1C-+IN-Pad10)") (class "Default")
      (node (ref "IC1") (pin "10") (pinfunction "+IN_10") (pintype "input"))
    )
    (net (code "153") (name "unconnected-(IC2A-+IN-Pad3)") (class "Default")
      (node (ref "IC2") (pin "3") (pinfunction "+IN_3") (pintype "input"))
    )
    (net (code "154") (name "unconnected-(J8-PadID)") (class "Default")
      (node (ref "J8") (pin "ID") (pinfunction "ID_ID") (pintype "bidirectional"))
    )
    (net (code "155") (name "unconnected-(P1-Pad6)") (class "Default")
      (node (ref "P1") (pin "6") (pinfunction "6_6") (pintype "bidirectional"))
    )
    (net (code "156") (name "unconnected-(P1-Pad8)") (class "Default")
      (node (ref "P1") (pin "8") (pinfunction "8_8") (pintype "bidirectional"))
    )
    (net (code "157") (name "unconnected-(U3-EXTREF0-P0(3)-Pad74)") (class "Default")
      (node (ref "U3") (pin "74") (pinfunction "EXTREF0-P0(3)_74") (pintype "bidirectional"))
    )
    (net (code "158") (name "unconnected-(U3-IDAC0-P0(6)-Pad78)") (class "Default")
      (node (ref "U3") (pin "78") (pinfunction "IDAC0-P0(6)_78") (pintype "bidirectional"))
    )
    (net (code "159") (name "unconnected-(U3-IND-Pad11)") (class "Default")
      (node (ref "U3") (pin "11") (pinfunction "IND_11") (pintype "bidirectional"))
    )
    (net (code "160") (name "unconnected-(U3-NC-Pad40)") (class "Default")
      (node (ref "U3") (pin "40") (pinfunction "NC_40") (pintype "bidirectional"))
    )
    (net (code "161") (name "unconnected-(U3-NC-Pad41)") (class "Default")
      (node (ref "U3") (pin "41") (pinfunction "NC_41") (pintype "bidirectional"))
    )
    (net (code "162") (name "unconnected-(U3-NC-Pad57)") (class "Default")
      (node (ref "U3") (pin "57") (pinfunction "NC_57") (pintype "bidirectional"))
    )
    (net (code "163") (name "unconnected-(U3-NC-Pad58)") (class "Default")
      (node (ref "U3") (pin "58") (pinfunction "NC_58") (pintype "bidirectional"))
    )
    (net (code "164") (name "unconnected-(U3-NC-Pad59)") (class "Default")
      (node (ref "U3") (pin "59") (pinfunction "NC_59") (pintype "bidirectional"))
    )
    (net (code "165") (name "unconnected-(U3-NC-Pad60)") (class "Default")
      (node (ref "U3") (pin "60") (pinfunction "NC_60") (pintype "bidirectional"))
    )
    (net (code "166") (name "unconnected-(U3-NC-Pad61)") (class "Default")
      (node (ref "U3") (pin "61") (pinfunction "NC_61") (pintype "bidirectional"))
    )
    (net (code "167") (name "unconnected-(U3-NC-Pad62)") (class "Default")
      (node (ref "U3") (pin "62") (pinfunction "NC_62") (pintype "bidirectional"))
    )
    (net (code "168") (name "unconnected-(U3-P0(5)-Pad77)") (class "Default")
      (node (ref "U3") (pin "77") (pinfunction "P0(5)_77") (pintype "bidirectional"))
    )
    (net (code "169") (name "unconnected-(U3-P0(7)-Pad79)") (class "Default")
      (node (ref "U3") (pin "79") (pinfunction "P0(7)_79") (pintype "bidirectional"))
    )
    (net (code "170") (name "unconnected-(U3-P1(3)-TDO-SWO-Pad23)") (class "Default")
      (node (ref "U3") (pin "23") (pinfunction "P1(3)-TDO-SWO_23") (pintype "bidirectional"))
    )
    (net (code "171") (name "unconnected-(U3-P1(5)-INTRST-Pad25)") (class "Default")
      (node (ref "U3") (pin "25") (pinfunction "P1(5)-INTRST_25") (pintype "bidirectional"))
    )
    (net (code "172") (name "unconnected-(U3-P2(0)-Pad95)") (class "Default")
      (node (ref "U3") (pin "95") (pinfunction "P2(0)_95") (pintype "bidirectional"))
    )
    (net (code "173") (name "unconnected-(U3-P2(1)-Pad96)") (class "Default")
      (node (ref "U3") (pin "96") (pinfunction "P2(1)_96") (pintype "bidirectional"))
    )
    (net (code "174") (name "unconnected-(U3-P2(2)-Pad97)") (class "Default")
      (node (ref "U3") (pin "97") (pinfunction "P2(2)_97") (pintype "bidirectional"))
    )
    (net (code "175") (name "unconnected-(U3-P2(3)-Pad98)") (class "Default")
      (node (ref "U3") (pin "98") (pinfunction "P2(3)_98") (pintype "bidirectional"))
    )
    (net (code "176") (name "unconnected-(U3-P3(0)-Pad44)") (class "Default")
      (node (ref "U3") (pin "44") (pinfunction "P3(0)_44") (pintype "bidirectional"))
    )
    (net (code "177") (name "unconnected-(U3-P3(1)-Pad45)") (class "Default")
      (node (ref "U3") (pin "45") (pinfunction "P3(1)_45") (pintype "bidirectional"))
    )
    (net (code "178") (name "unconnected-(U3-P3(2)-EXTREF1-Pad46)") (class "Default")
      (node (ref "U3") (pin "46") (pinfunction "P3(2)-EXTREF1_46") (pintype "bidirectional"))
    )
    (net (code "179") (name "unconnected-(U3-P3(3)-Pad47)") (class "Default")
      (node (ref "U3") (pin "47") (pinfunction "P3(3)_47") (pintype "bidirectional"))
    )
    (net (code "180") (name "unconnected-(U3-P3(4)-Pad48)") (class "Default")
      (node (ref "U3") (pin "48") (pinfunction "P3(4)_48") (pintype "bidirectional"))
    )
    (net (code "181") (name "unconnected-(U3-P3(5)-Pad49)") (class "Default")
      (node (ref "U3") (pin "49") (pinfunction "P3(5)_49") (pintype "bidirectional"))
    )
    (net (code "182") (name "unconnected-(U3-P3(7)-Pad52)") (class "Default")
      (node (ref "U3") (pin "52") (pinfunction "P3(7)_52") (pintype "bidirectional"))
    )
    (net (code "183") (name "unconnected-(U3-P4(1)-Pad70)") (class "Default")
      (node (ref "U3") (pin "70") (pinfunction "P4(1)_70") (pintype "bidirectional"))
    )
    (net (code "184") (name "unconnected-(U3-P5(0)-Pad16)") (class "Default")
      (node (ref "U3") (pin "16") (pinfunction "P5(0)_16") (pintype "bidirectional"))
    )
    (net (code "185") (name "unconnected-(U3-P5(2)-Pad18)") (class "Default")
      (node (ref "U3") (pin "18") (pinfunction "P5(2)_18") (pintype "bidirectional"))
    )
    (net (code "186") (name "unconnected-(U3-P5(3)-Pad19)") (class "Default")
      (node (ref "U3") (pin "19") (pinfunction "P5(3)_19") (pintype "bidirectional"))
    )
    (net (code "187") (name "unconnected-(U3-P5(7)-Pad34)") (class "Default")
      (node (ref "U3") (pin "34") (pinfunction "P5(7)_34") (pintype "bidirectional"))
    )
    (net (code "188") (name "unconnected-(U3-P6(0)-Pad89)") (class "Default")
      (node (ref "U3") (pin "89") (pinfunction "P6(0)_89") (pintype "bidirectional"))
    )
    (net (code "189") (name "unconnected-(U3-P6(1)-Pad90)") (class "Default")
      (node (ref "U3") (pin "90") (pinfunction "P6(1)_90") (pintype "bidirectional"))
    )
    (net (code "190") (name "unconnected-(U3-P6(2)-Pad91)") (class "Default")
      (node (ref "U3") (pin "91") (pinfunction "P6(2)_91") (pintype "bidirectional"))
    )
    (net (code "191") (name "unconnected-(U3-P12(7)-Pad30)") (class "Default")
      (node (ref "U3") (pin "30") (pinfunction "P12(7)_30") (pintype "bidirectional"))
    )
    (net (code "192") (name "unconnected-(U3-P15(0)-XTALO-Pad42)") (class "Default")
      (node (ref "U3") (pin "42") (pinfunction "P15(0)-XTALO_42") (pintype "bidirectional"))
    )
    (net (code "193") (name "unconnected-(U3-P15(5)-Pad94)") (class "Default")
      (node (ref "U3") (pin "94") (pinfunction "P15(5)_94") (pintype "bidirectional"))
    )
    (net (code "194") (name "unconnected-(U3-SCL1-P12(0)-Pad53)") (class "Default")
      (node (ref "U3") (pin "53") (pinfunction "SCL1-P12(0)_53") (pintype "bidirectional"))
    )
    (net (code "195") (name "unconnected-(U3-SDA1-P12(1)-Pad54)") (class "Default")
      (node (ref "U3") (pin "54") (pinfunction "SDA1-P12(1)_54") (pintype "bidirectional"))
    )
    (net (code "196") (name "unconnected-(U3-SIO-P12(2)-Pad67)") (class "Default")
      (node (ref "U3") (pin "67") (pinfunction "SIO-P12(2)_67") (pintype "bidirectional"))
    )
    (net (code "197") (name "unconnected-(U3-SIO-P12(3)-Pad68)") (class "Default")
      (node (ref "U3") (pin "68") (pinfunction "SIO-P12(3)_68") (pintype "bidirectional"))
    )
    (net (code "198") (name "{slash}XRES") (class "Default")
      (node (ref "J6") (pin "3") (pinfunction "3_3") (pintype "bidirectional"))
      (node (ref "P1") (pin "10") (pinfunction "10_10") (pintype "bidirectional"))
      (node (ref "U3") (pin "15") (pinfunction "/XRES_15") (pintype "bidirectional"))
    )
  )
)
